# interface_board.net
KiCad netlist of a schematic drawn in EAGLE
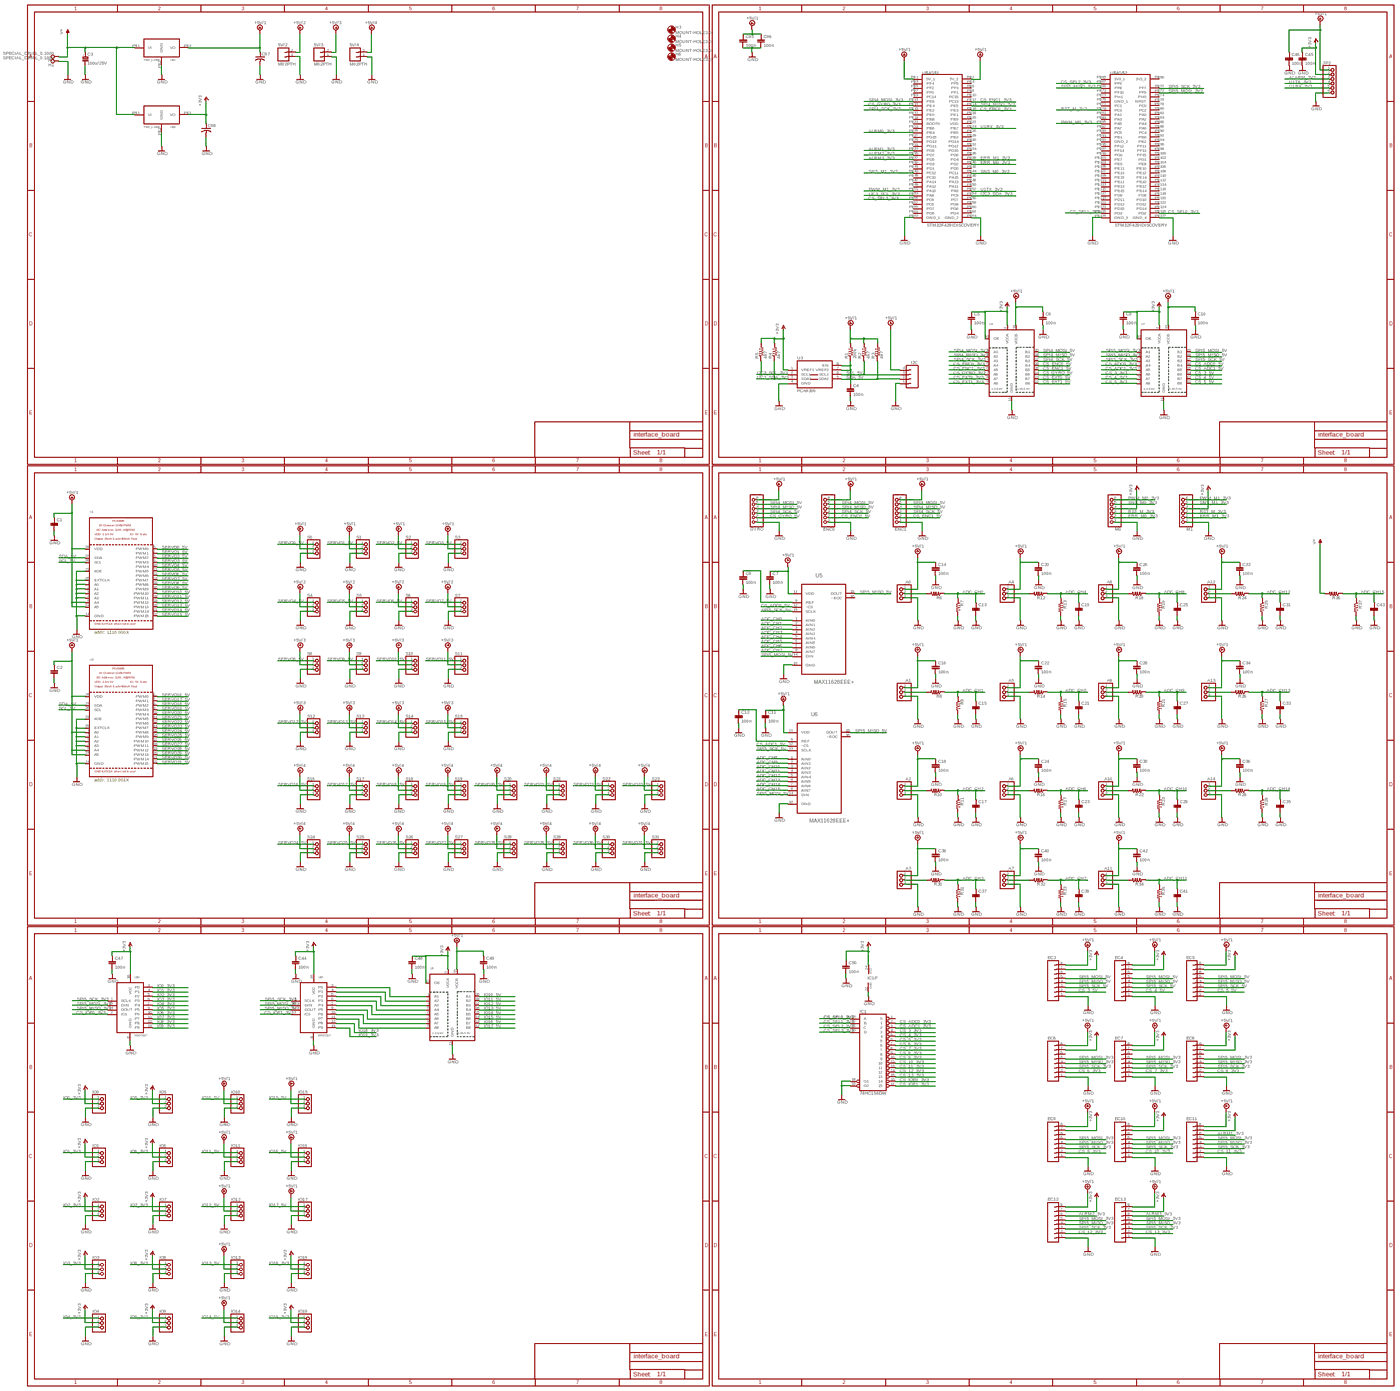
[diagram p0: schematic, sheet 1, overview]
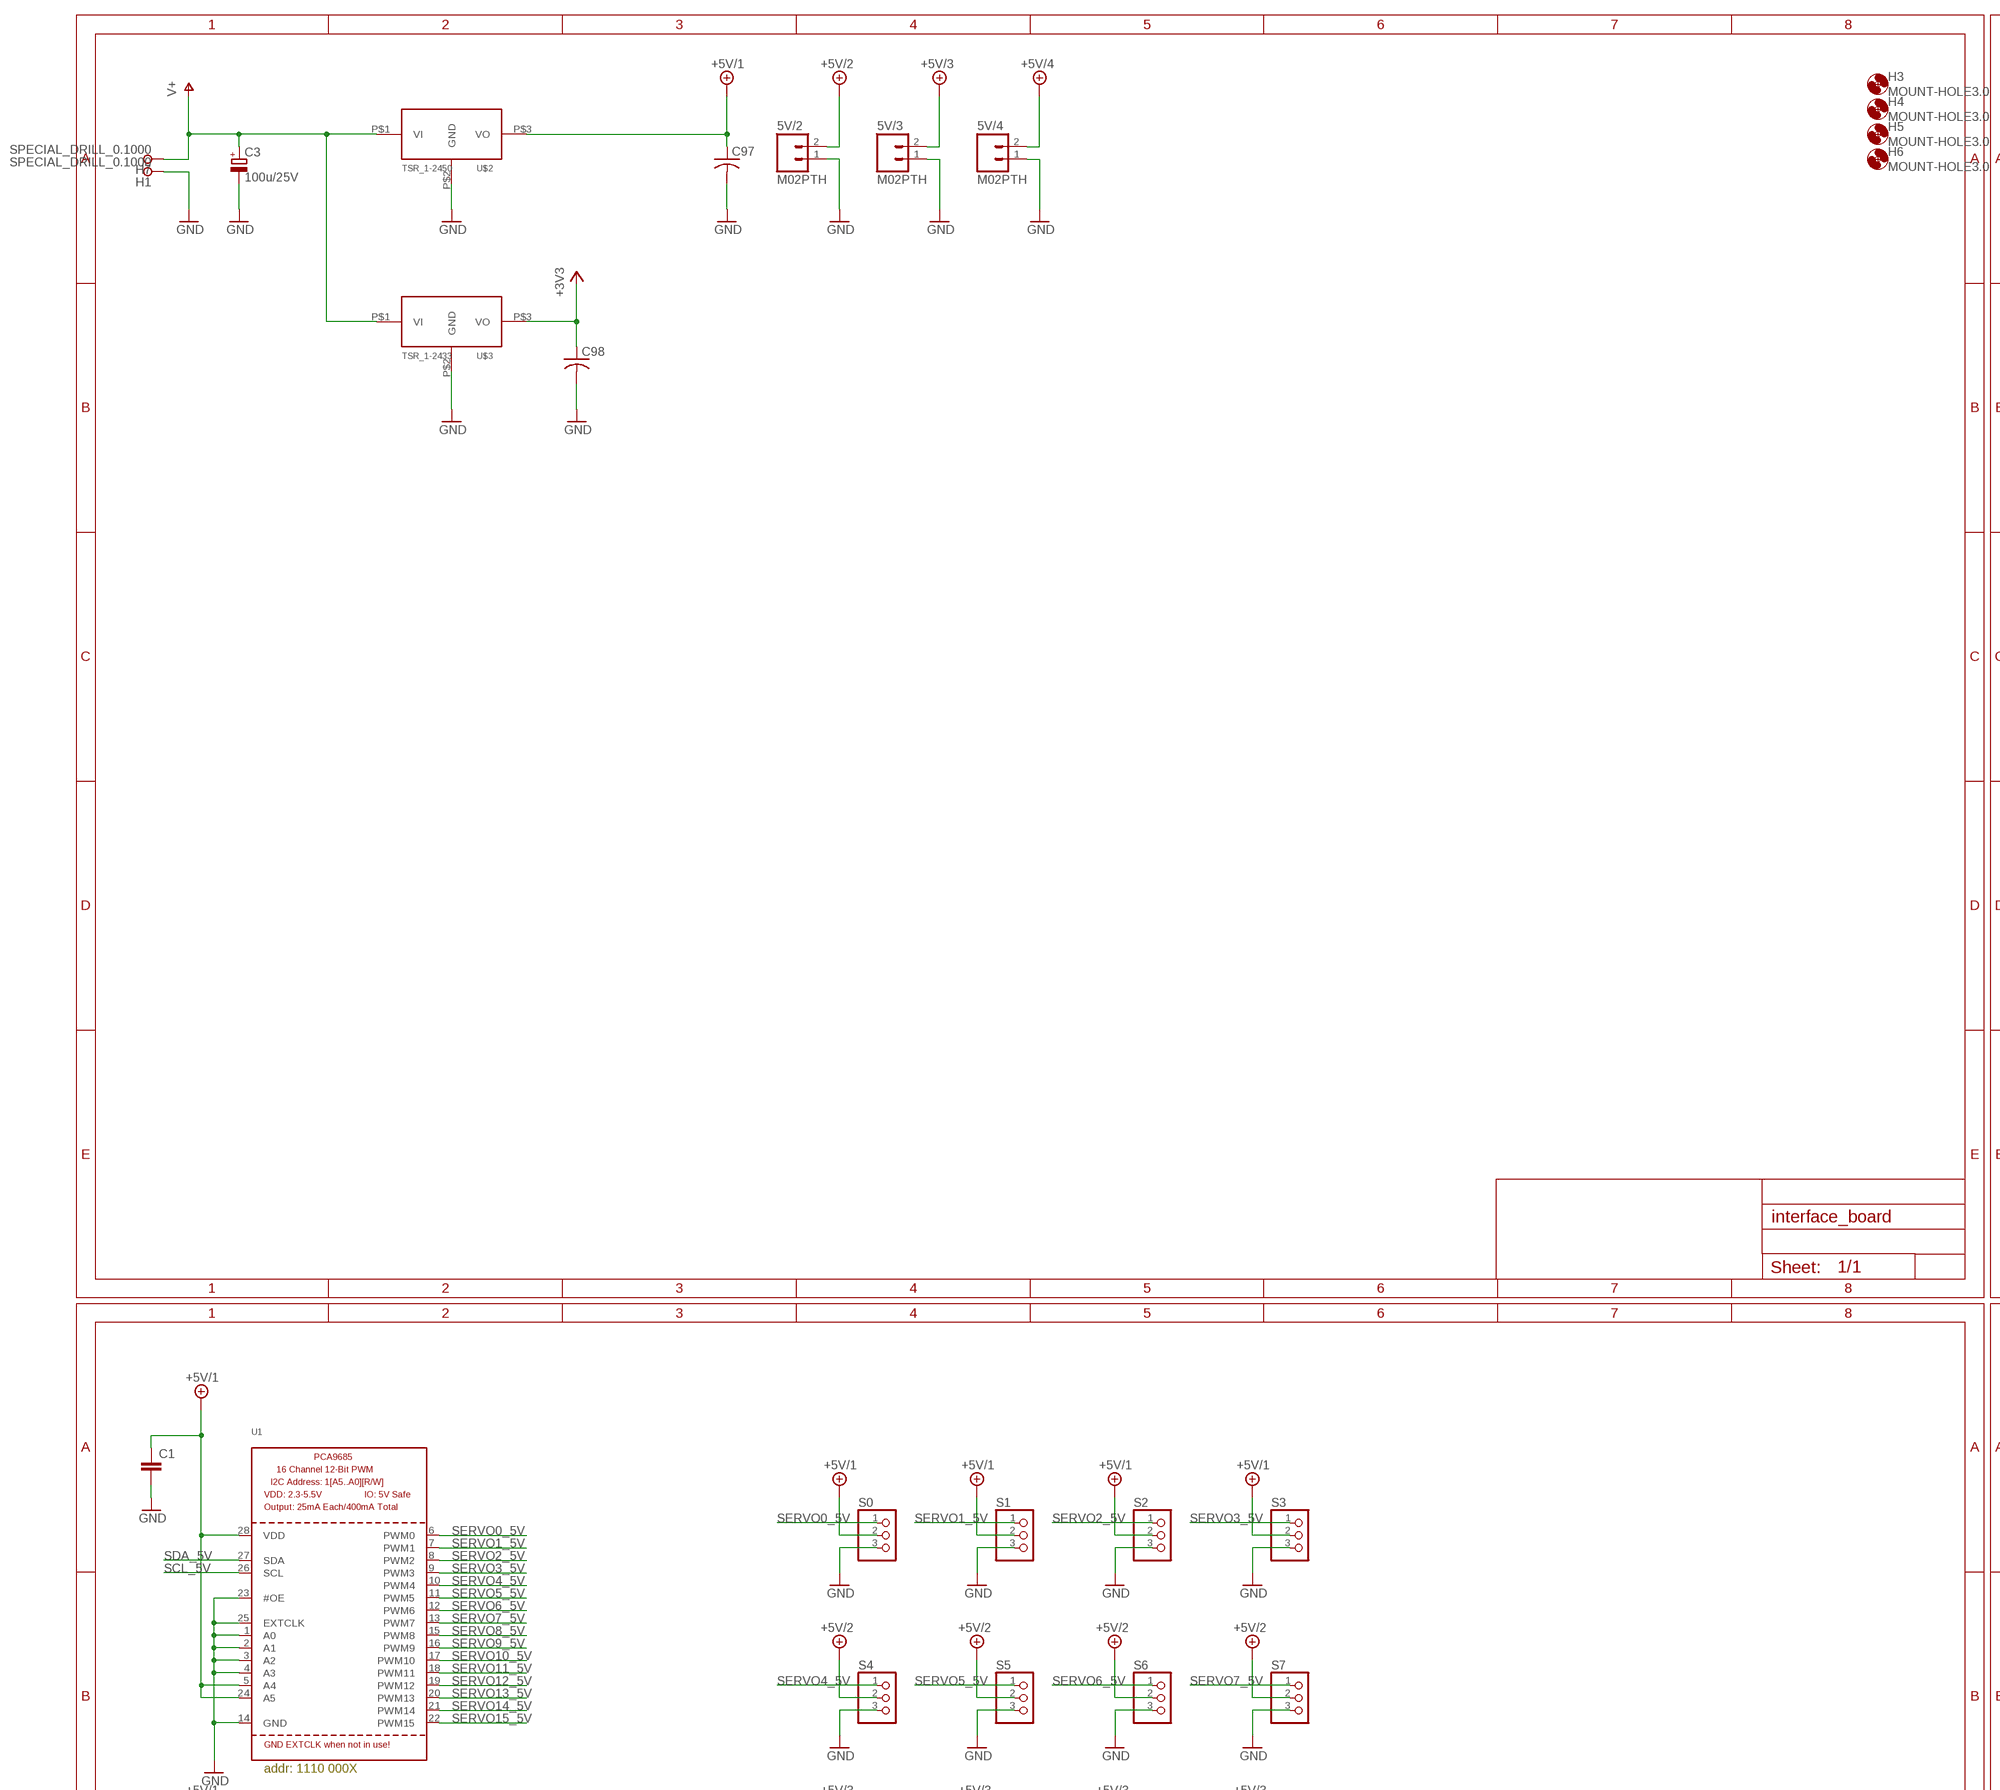
[diagram p1: schematic, sheet 1, part 1 of 4]
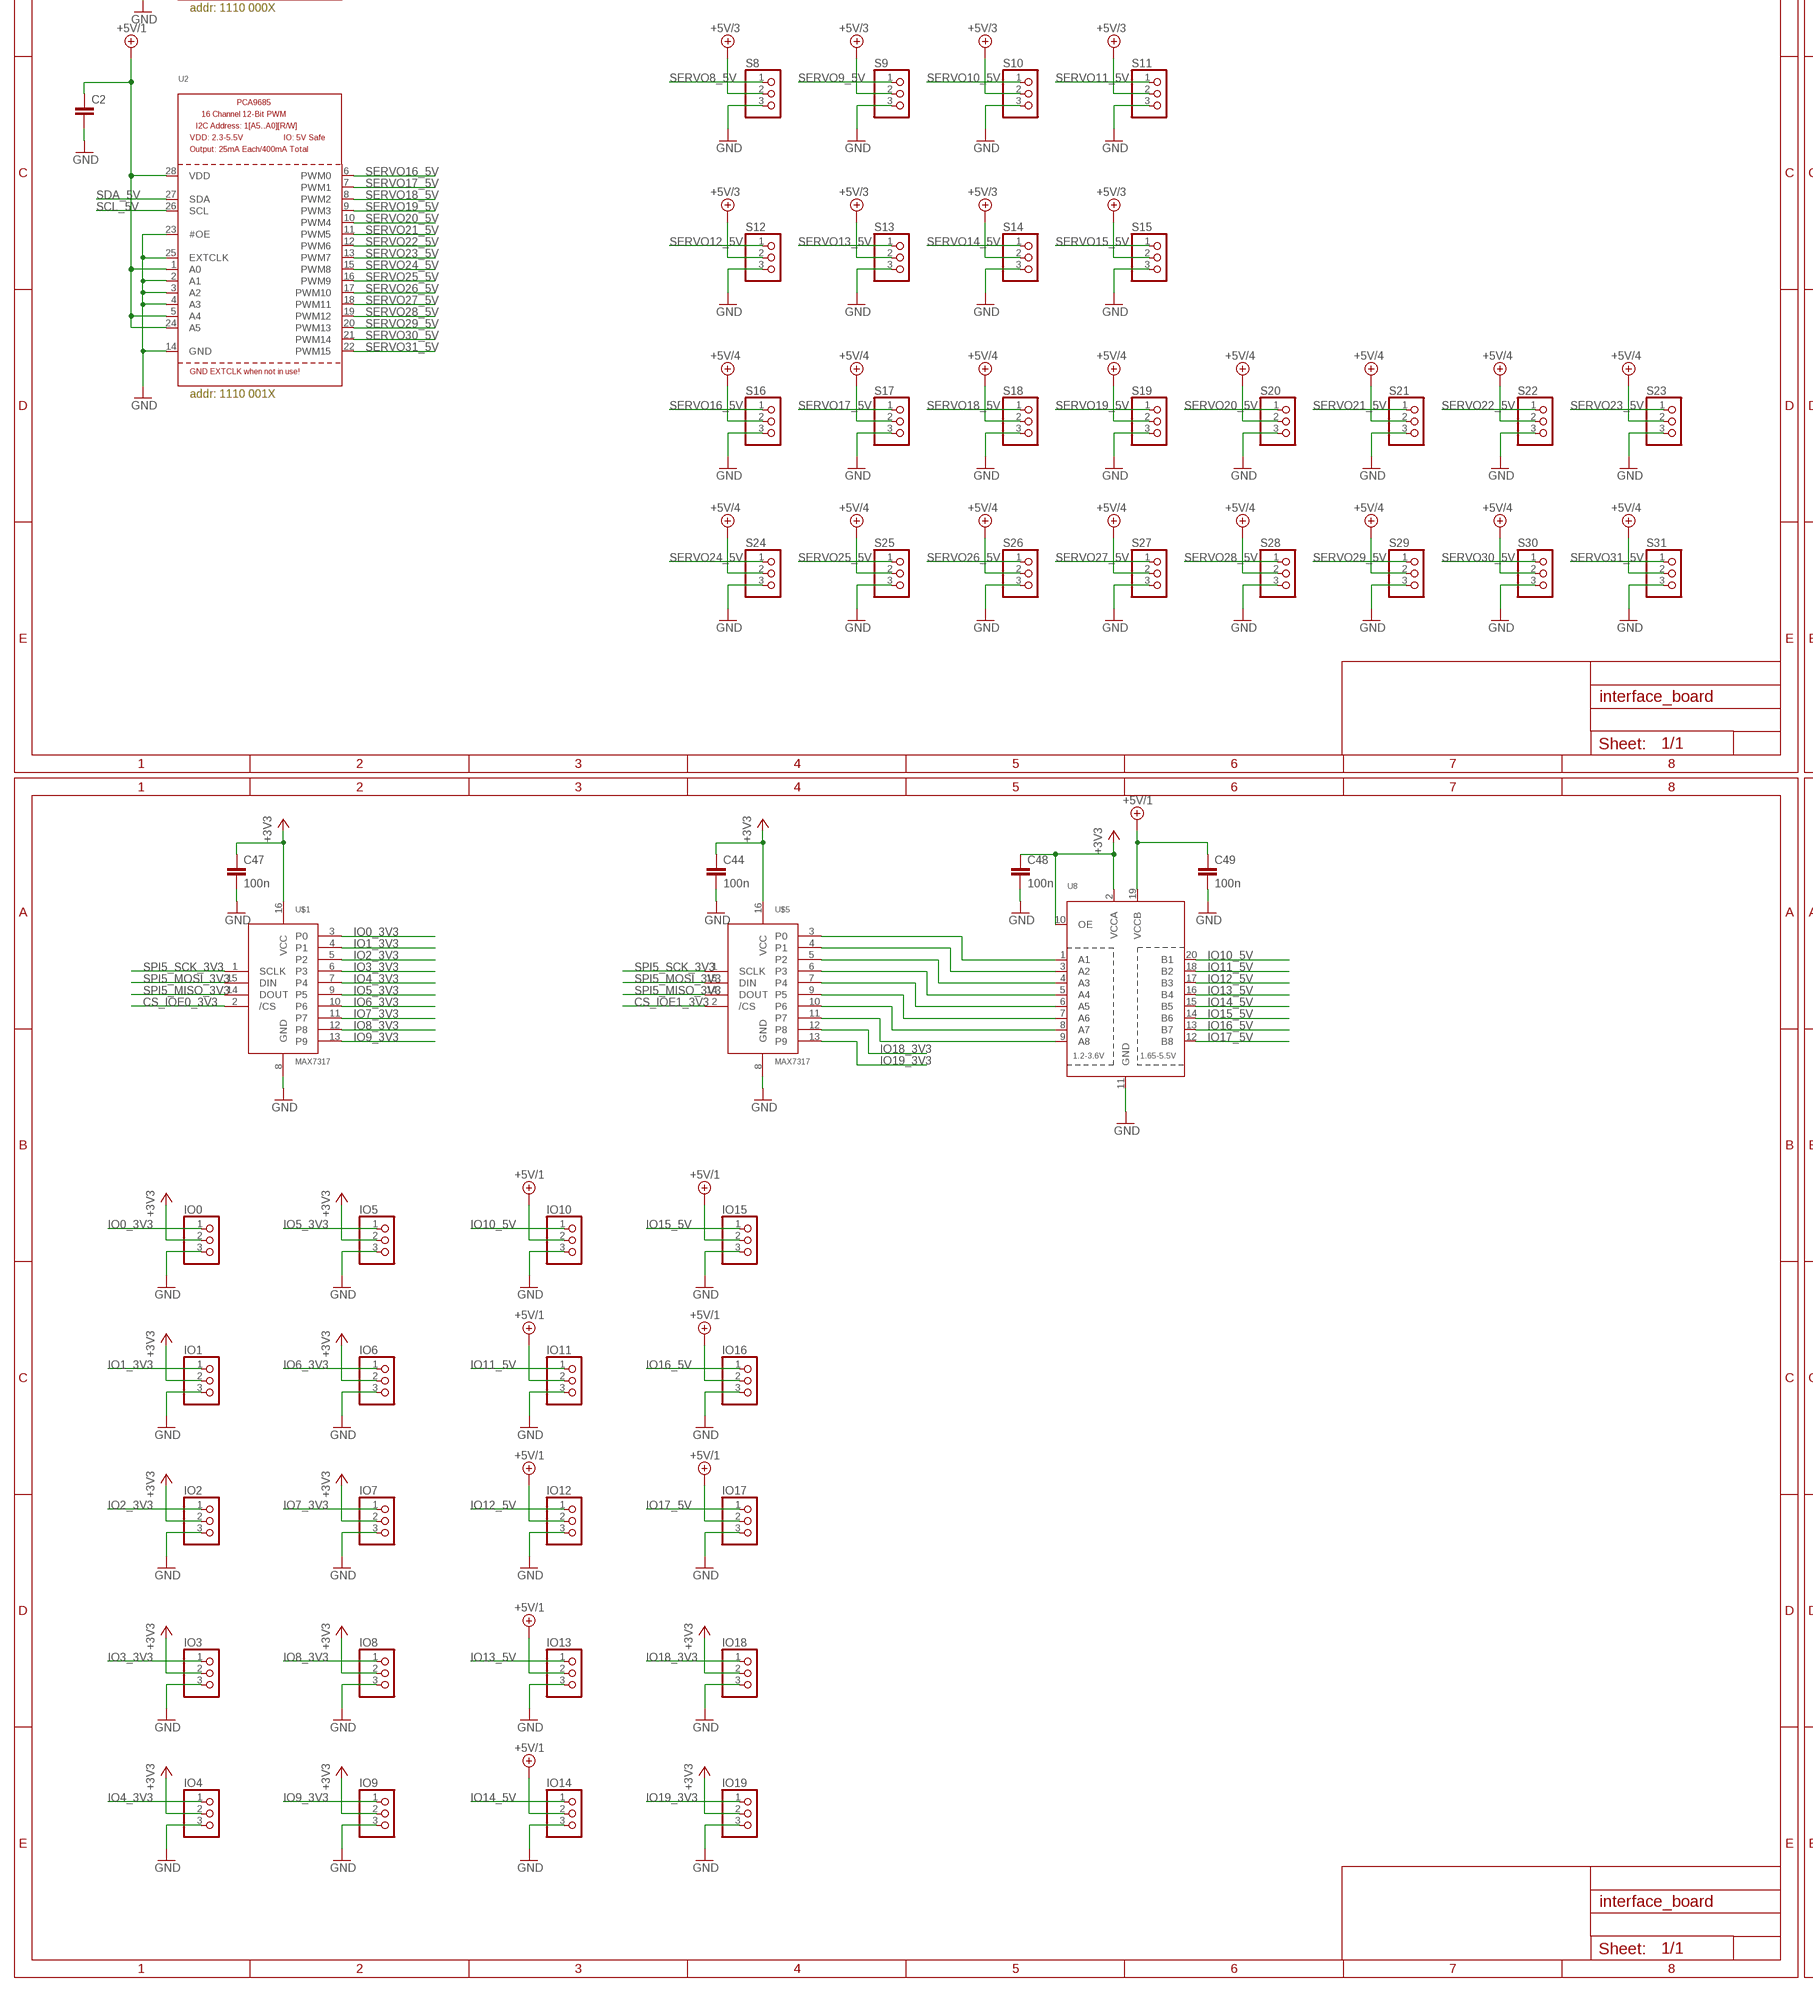
[diagram p2: schematic, sheet 1, part 2 of 4]
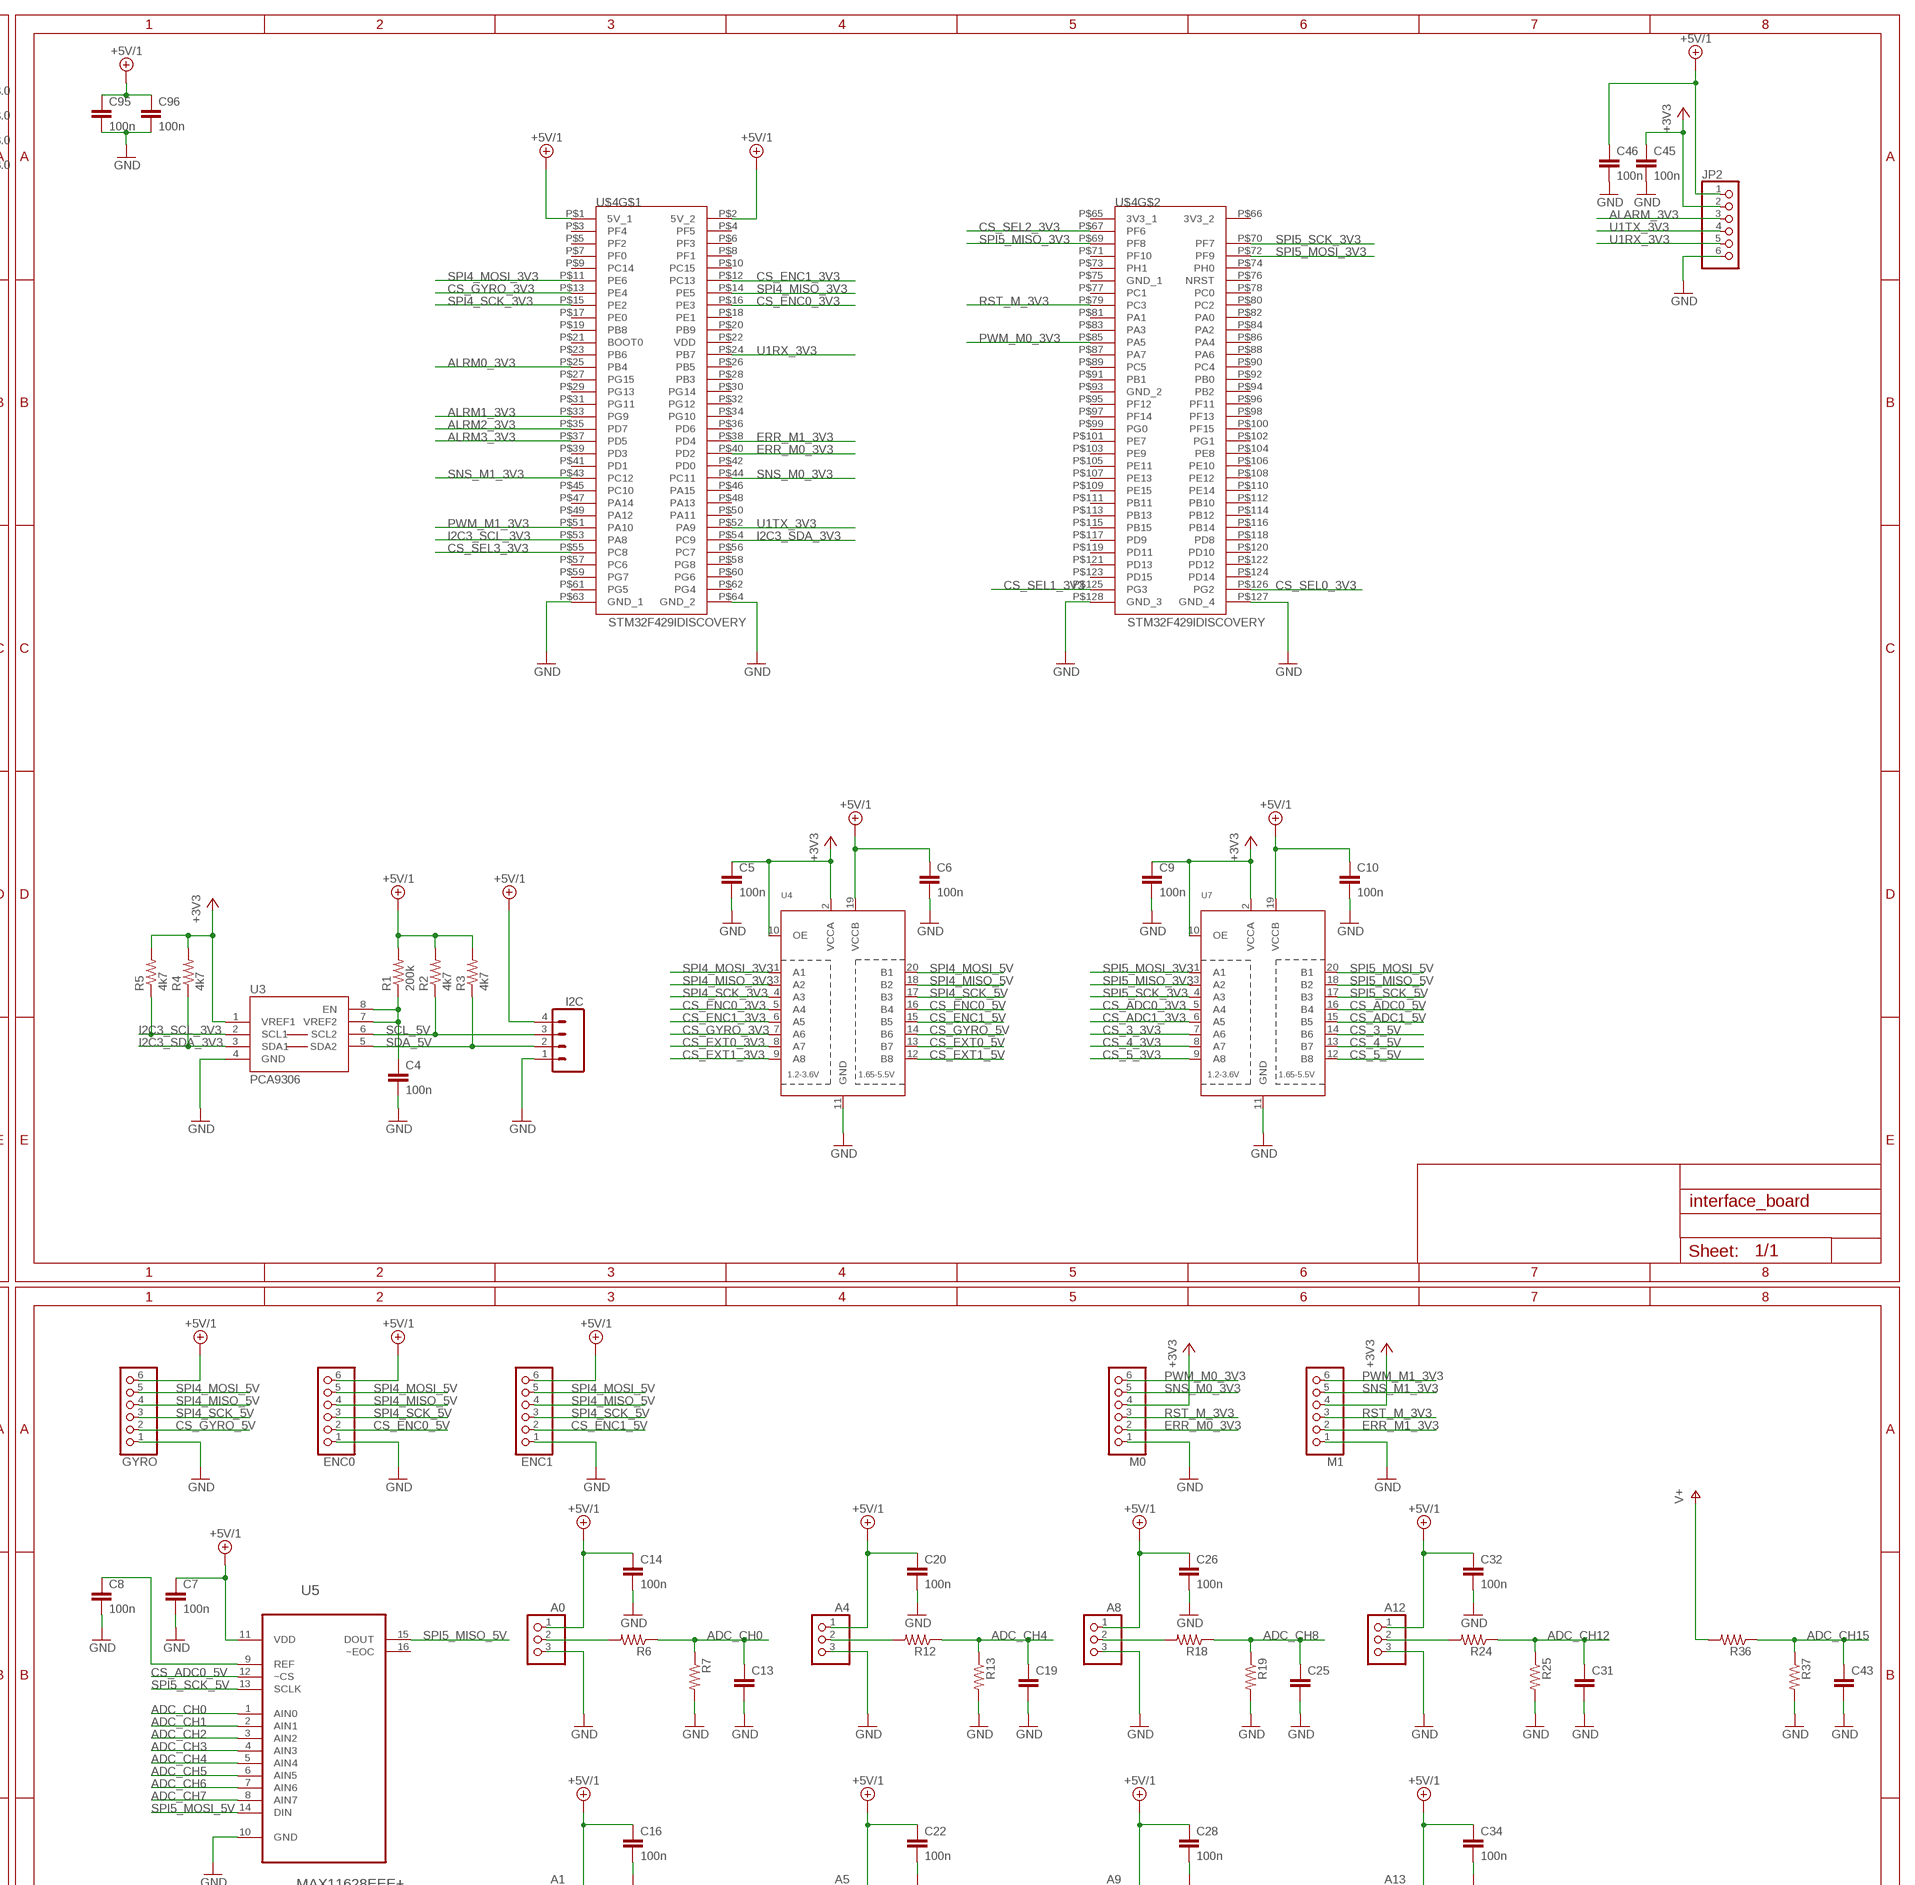
[diagram p3: schematic, sheet 1, part 3 of 4]
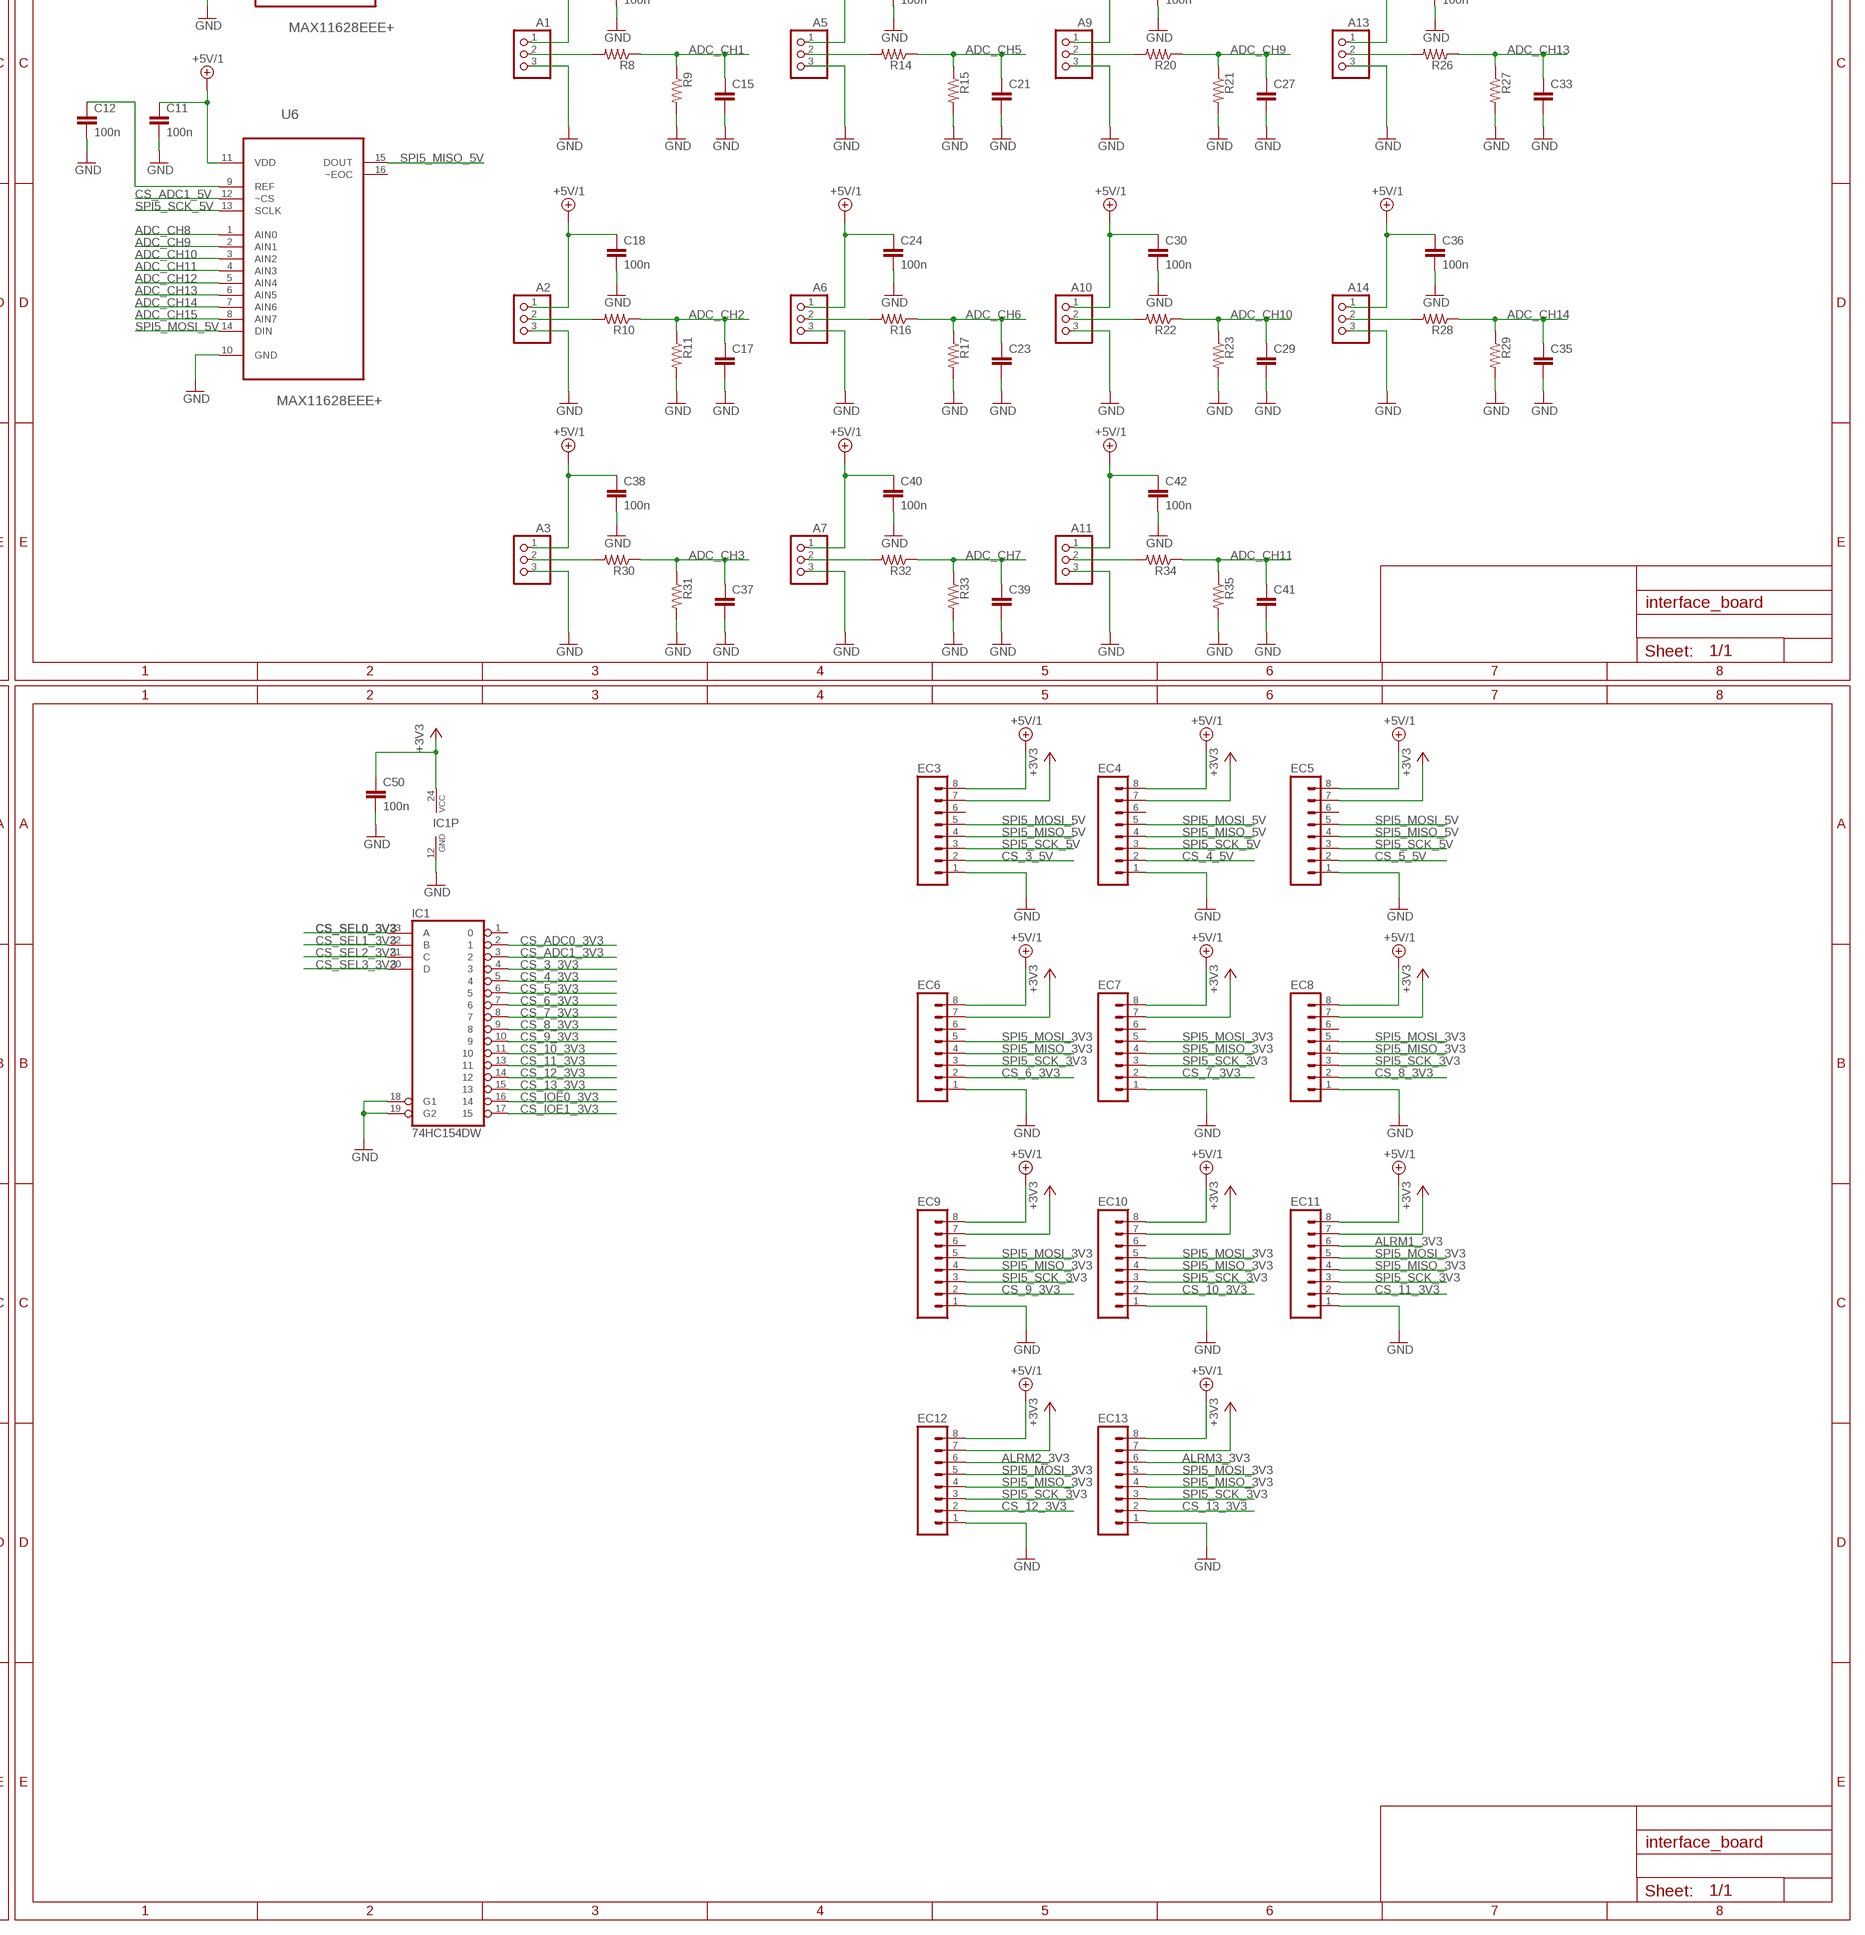
[diagram p4: schematic, sheet 1, part 4 of 4]

(export (version "E")
  (design (tool "Eeschema 10.0.6"))
  (components
    (comp (ref "5V/2")
      (value "M02PTH")
      (footprint "eagle-import:1X02")
      (libsource (lib "eagle-import") (part "M02PTH"))
    )
    (comp (ref "5V/3")
      (value "M02PTH")
      (footprint "eagle-import:1X02")
      (libsource (lib "eagle-import") (part "M02PTH"))
    )
    (comp (ref "5V/4")
      (value "M02PTH")
      (footprint "eagle-import:1X02")
      (libsource (lib "eagle-import") (part "M02PTH"))
    )
    (comp (ref "A0")
      (value "PINHD-1X3")
      (footprint "eagle-import:1X03")
      (libsource (lib "eagle-import") (part "PINHD-1X3"))
    )
    (comp (ref "A1")
      (value "PINHD-1X3")
      (footprint "eagle-import:1X03")
      (libsource (lib "eagle-import") (part "PINHD-1X3"))
    )
    (comp (ref "A2")
      (value "PINHD-1X3")
      (footprint "eagle-import:1X03")
      (libsource (lib "eagle-import") (part "PINHD-1X3"))
    )
    (comp (ref "A3")
      (value "PINHD-1X3")
      (footprint "eagle-import:1X03")
      (libsource (lib "eagle-import") (part "PINHD-1X3"))
    )
    (comp (ref "A4")
      (value "PINHD-1X3")
      (footprint "eagle-import:1X03")
      (libsource (lib "eagle-import") (part "PINHD-1X3"))
    )
    (comp (ref "A5")
      (value "PINHD-1X3")
      (footprint "eagle-import:1X03")
      (libsource (lib "eagle-import") (part "PINHD-1X3"))
    )
    (comp (ref "A6")
      (value "PINHD-1X3")
      (footprint "eagle-import:1X03")
      (libsource (lib "eagle-import") (part "PINHD-1X3"))
    )
    (comp (ref "A7")
      (value "PINHD-1X3")
      (footprint "eagle-import:1X03")
      (libsource (lib "eagle-import") (part "PINHD-1X3"))
    )
    (comp (ref "A8")
      (value "PINHD-1X3")
      (footprint "eagle-import:1X03")
      (libsource (lib "eagle-import") (part "PINHD-1X3"))
    )
    (comp (ref "A9")
      (value "PINHD-1X3")
      (footprint "eagle-import:1X03")
      (libsource (lib "eagle-import") (part "PINHD-1X3"))
    )
    (comp (ref "A10")
      (value "PINHD-1X3")
      (footprint "eagle-import:1X03")
      (libsource (lib "eagle-import") (part "PINHD-1X3"))
    )
    (comp (ref "A11")
      (value "PINHD-1X3")
      (footprint "eagle-import:1X03")
      (libsource (lib "eagle-import") (part "PINHD-1X3"))
    )
    (comp (ref "A12")
      (value "PINHD-1X3")
      (footprint "eagle-import:1X03")
      (libsource (lib "eagle-import") (part "PINHD-1X3"))
    )
    (comp (ref "A13")
      (value "PINHD-1X3")
      (footprint "eagle-import:1X03")
      (libsource (lib "eagle-import") (part "PINHD-1X3"))
    )
    (comp (ref "A14")
      (value "PINHD-1X3")
      (footprint "eagle-import:1X03")
      (libsource (lib "eagle-import") (part "PINHD-1X3"))
    )
    (comp (ref "C1")
      (value "C-EUC0603K")
      (footprint "eagle-import:C0603K")
      (libsource (lib "eagle-import") (part "C-EUC0603K"))
    )
    (comp (ref "C2")
      (value "C-EUC0603K")
      (footprint "eagle-import:C0603K")
      (libsource (lib "eagle-import") (part "C-EUC0603K"))
    )
    (comp (ref "C3")
      (value "100u/25V")
      (footprint "eagle-import:PANASONIC_E")
      (libsource (lib "eagle-import") (part "CPOL-EUE"))
    )
    (comp (ref "C4")
      (value "100n")
      (footprint "eagle-import:C0603K")
      (libsource (lib "eagle-import") (part "C-EUC0603K"))
    )
    (comp (ref "C5")
      (value "100n")
      (footprint "eagle-import:C0603K")
      (libsource (lib "eagle-import") (part "C-EUC0603K"))
    )
    (comp (ref "C6")
      (value "100n")
      (footprint "eagle-import:C0603K")
      (libsource (lib "eagle-import") (part "C-EUC0603K"))
    )
    (comp (ref "C7")
      (value "100n")
      (footprint "eagle-import:C0603K")
      (libsource (lib "eagle-import") (part "C-EUC0603K"))
    )
    (comp (ref "C8")
      (value "100n")
      (footprint "eagle-import:C0603K")
      (libsource (lib "eagle-import") (part "C-EUC0603K"))
    )
    (comp (ref "C9")
      (value "100n")
      (footprint "eagle-import:C0603K")
      (libsource (lib "eagle-import") (part "C-EUC0603K"))
    )
    (comp (ref "C10")
      (value "100n")
      (footprint "eagle-import:C0603K")
      (libsource (lib "eagle-import") (part "C-EUC0603K"))
    )
    (comp (ref "C11")
      (value "100n")
      (footprint "eagle-import:C0603K")
      (libsource (lib "eagle-import") (part "C-EUC0603K"))
    )
    (comp (ref "C12")
      (value "100n")
      (footprint "eagle-import:C0603K")
      (libsource (lib "eagle-import") (part "C-EUC0603K"))
    )
    (comp (ref "C13")
      (value "C-EUC0603K")
      (footprint "eagle-import:C0603K")
      (libsource (lib "eagle-import") (part "C-EUC0603K"))
    )
    (comp (ref "C14")
      (value "100n")
      (footprint "eagle-import:C0603K")
      (libsource (lib "eagle-import") (part "C-EUC0603K"))
    )
    (comp (ref "C15")
      (value "C-EUC0603K")
      (footprint "eagle-import:C0603K")
      (libsource (lib "eagle-import") (part "C-EUC0603K"))
    )
    (comp (ref "C16")
      (value "100n")
      (footprint "eagle-import:C0603K")
      (libsource (lib "eagle-import") (part "C-EUC0603K"))
    )
    (comp (ref "C17")
      (value "C-EUC0603K")
      (footprint "eagle-import:C0603K")
      (libsource (lib "eagle-import") (part "C-EUC0603K"))
    )
    (comp (ref "C18")
      (value "100n")
      (footprint "eagle-import:C0603K")
      (libsource (lib "eagle-import") (part "C-EUC0603K"))
    )
    (comp (ref "C19")
      (value "C-EUC0603K")
      (footprint "eagle-import:C0603K")
      (libsource (lib "eagle-import") (part "C-EUC0603K"))
    )
    (comp (ref "C20")
      (value "100n")
      (footprint "eagle-import:C0603K")
      (libsource (lib "eagle-import") (part "C-EUC0603K"))
    )
    (comp (ref "C21")
      (value "C-EUC0603K")
      (footprint "eagle-import:C0603K")
      (libsource (lib "eagle-import") (part "C-EUC0603K"))
    )
    (comp (ref "C22")
      (value "100n")
      (footprint "eagle-import:C0603K")
      (libsource (lib "eagle-import") (part "C-EUC0603K"))
    )
    (comp (ref "C23")
      (value "C-EUC0603K")
      (footprint "eagle-import:C0603K")
      (libsource (lib "eagle-import") (part "C-EUC0603K"))
    )
    (comp (ref "C24")
      (value "100n")
      (footprint "eagle-import:C0603K")
      (libsource (lib "eagle-import") (part "C-EUC0603K"))
    )
    (comp (ref "C25")
      (value "C-EUC0603K")
      (footprint "eagle-import:C0603K")
      (libsource (lib "eagle-import") (part "C-EUC0603K"))
    )
    (comp (ref "C26")
      (value "100n")
      (footprint "eagle-import:C0603K")
      (libsource (lib "eagle-import") (part "C-EUC0603K"))
    )
    (comp (ref "C27")
      (value "C-EUC0603K")
      (footprint "eagle-import:C0603K")
      (libsource (lib "eagle-import") (part "C-EUC0603K"))
    )
    (comp (ref "C28")
      (value "100n")
      (footprint "eagle-import:C0603K")
      (libsource (lib "eagle-import") (part "C-EUC0603K"))
    )
    (comp (ref "C29")
      (value "C-EUC0603K")
      (footprint "eagle-import:C0603K")
      (libsource (lib "eagle-import") (part "C-EUC0603K"))
    )
    (comp (ref "C30")
      (value "100n")
      (footprint "eagle-import:C0603K")
      (libsource (lib "eagle-import") (part "C-EUC0603K"))
    )
    (comp (ref "C31")
      (value "C-EUC0603K")
      (footprint "eagle-import:C0603K")
      (libsource (lib "eagle-import") (part "C-EUC0603K"))
    )
    (comp (ref "C32")
      (value "100n")
      (footprint "eagle-import:C0603K")
      (libsource (lib "eagle-import") (part "C-EUC0603K"))
    )
    (comp (ref "C33")
      (value "C-EUC0603K")
      (footprint "eagle-import:C0603K")
      (libsource (lib "eagle-import") (part "C-EUC0603K"))
    )
    (comp (ref "C34")
      (value "100n")
      (footprint "eagle-import:C0603K")
      (libsource (lib "eagle-import") (part "C-EUC0603K"))
    )
    (comp (ref "C35")
      (value "C-EUC0603K")
      (footprint "eagle-import:C0603K")
      (libsource (lib "eagle-import") (part "C-EUC0603K"))
    )
    (comp (ref "C36")
      (value "100n")
      (footprint "eagle-import:C0603K")
      (libsource (lib "eagle-import") (part "C-EUC0603K"))
    )
    (comp (ref "C37")
      (value "C-EUC0603K")
      (footprint "eagle-import:C0603K")
      (libsource (lib "eagle-import") (part "C-EUC0603K"))
    )
    (comp (ref "C38")
      (value "100n")
      (footprint "eagle-import:C0603K")
      (libsource (lib "eagle-import") (part "C-EUC0603K"))
    )
    (comp (ref "C39")
      (value "C-EUC0603K")
      (footprint "eagle-import:C0603K")
      (libsource (lib "eagle-import") (part "C-EUC0603K"))
    )
    (comp (ref "C40")
      (value "100n")
      (footprint "eagle-import:C0603K")
      (libsource (lib "eagle-import") (part "C-EUC0603K"))
    )
    (comp (ref "C41")
      (value "C-EUC0603K")
      (footprint "eagle-import:C0603K")
      (libsource (lib "eagle-import") (part "C-EUC0603K"))
    )
    (comp (ref "C42")
      (value "100n")
      (footprint "eagle-import:C0603K")
      (libsource (lib "eagle-import") (part "C-EUC0603K"))
    )
    (comp (ref "C43")
      (value "C-EUC0603K")
      (footprint "eagle-import:C0603K")
      (libsource (lib "eagle-import") (part "C-EUC0603K"))
    )
    (comp (ref "C44")
      (value "100n")
      (footprint "eagle-import:C0603K")
      (libsource (lib "eagle-import") (part "C-EUC0603K"))
    )
    (comp (ref "C45")
      (value "100n")
      (footprint "eagle-import:C0603K")
      (libsource (lib "eagle-import") (part "C-EUC0603K"))
    )
    (comp (ref "C46")
      (value "100n")
      (footprint "eagle-import:C0603K")
      (libsource (lib "eagle-import") (part "C-EUC0603K"))
    )
    (comp (ref "C47")
      (value "100n")
      (footprint "eagle-import:C0603K")
      (libsource (lib "eagle-import") (part "C-EUC0603K"))
    )
    (comp (ref "C48")
      (value "100n")
      (footprint "eagle-import:C0603K")
      (libsource (lib "eagle-import") (part "C-EUC0603K"))
    )
    (comp (ref "C49")
      (value "100n")
      (footprint "eagle-import:C0603K")
      (libsource (lib "eagle-import") (part "C-EUC0603K"))
    )
    (comp (ref "C50")
      (value "100n")
      (footprint "eagle-import:C0603K")
      (libsource (lib "eagle-import") (part "C-EUC0603K"))
    )
    (comp (ref "C95")
      (value "100n")
      (footprint "eagle-import:C0603K")
      (libsource (lib "eagle-import") (part "C-EUC0603K"))
    )
    (comp (ref "C96")
      (value "100n")
      (footprint "eagle-import:C0603K")
      (libsource (lib "eagle-import") (part "C-EUC0603K"))
    )
    (comp (ref "C97")
      (value "C-USC0805")
      (footprint "eagle-import:C0805")
      (libsource (lib "eagle-import") (part "C-USC0805"))
    )
    (comp (ref "C98")
      (value "C-USC0805")
      (footprint "eagle-import:C0805")
      (libsource (lib "eagle-import") (part "C-USC0805"))
    )
    (comp (ref "EC3")
      (value "M081X08")
      (footprint "eagle-import:1X08")
      (libsource (lib "eagle-import") (part "M081X08"))
    )
    (comp (ref "EC4")
      (value "M081X08")
      (footprint "eagle-import:1X08")
      (libsource (lib "eagle-import") (part "M081X08"))
    )
    (comp (ref "EC5")
      (value "M081X08")
      (footprint "eagle-import:1X08")
      (libsource (lib "eagle-import") (part "M081X08"))
    )
    (comp (ref "EC6")
      (value "M081X08")
      (footprint "eagle-import:1X08")
      (libsource (lib "eagle-import") (part "M081X08"))
    )
    (comp (ref "EC7")
      (value "M081X08")
      (footprint "eagle-import:1X08")
      (libsource (lib "eagle-import") (part "M081X08"))
    )
    (comp (ref "EC8")
      (value "M081X08")
      (footprint "eagle-import:1X08")
      (libsource (lib "eagle-import") (part "M081X08"))
    )
    (comp (ref "EC9")
      (value "M081X08")
      (footprint "eagle-import:1X08")
      (libsource (lib "eagle-import") (part "M081X08"))
    )
    (comp (ref "EC10")
      (value "M081X08")
      (footprint "eagle-import:1X08")
      (libsource (lib "eagle-import") (part "M081X08"))
    )
    (comp (ref "EC11")
      (value "M081X08")
      (footprint "eagle-import:1X08")
      (libsource (lib "eagle-import") (part "M081X08"))
    )
    (comp (ref "EC12")
      (value "M081X08")
      (footprint "eagle-import:1X08")
      (libsource (lib "eagle-import") (part "M081X08"))
    )
    (comp (ref "EC13")
      (value "M081X08")
      (footprint "eagle-import:1X08")
      (libsource (lib "eagle-import") (part "M081X08"))
    )
    (comp (ref "ENC0")
      (value "PINHD-1X6")
      (footprint "eagle-import:1X06")
      (libsource (lib "eagle-import") (part "PINHD-1X6"))
    )
    (comp (ref "ENC1")
      (value "PINHD-1X6")
      (footprint "eagle-import:1X06")
      (libsource (lib "eagle-import") (part "PINHD-1X6"))
    )
    (comp (ref "GYRO")
      (value "PINHD-1X6")
      (footprint "eagle-import:1X06")
      (libsource (lib "eagle-import") (part "PINHD-1X6"))
    )
    (comp (ref "H1")
      (value "SPECIAL_DRILL_0.1000")
      (footprint "eagle-import:PAD_0.1000")
      (libsource (lib "eagle-import") (part "SPECIAL_DRILL_0.1000"))
    )
    (comp (ref "H3")
      (value "MOUNT-HOLE3.0")
      (footprint "eagle-import:3,0")
      (libsource (lib "eagle-import") (part "MOUNT-HOLE3.0"))
    )
    (comp (ref "H4")
      (value "MOUNT-HOLE3.0")
      (footprint "eagle-import:3,0")
      (libsource (lib "eagle-import") (part "MOUNT-HOLE3.0"))
    )
    (comp (ref "H5")
      (value "MOUNT-HOLE3.0")
      (footprint "eagle-import:3,0")
      (libsource (lib "eagle-import") (part "MOUNT-HOLE3.0"))
    )
    (comp (ref "H6")
      (value "MOUNT-HOLE3.0")
      (footprint "eagle-import:3,0")
      (libsource (lib "eagle-import") (part "MOUNT-HOLE3.0"))
    )
    (comp (ref "H7")
      (value "SPECIAL_DRILL_0.1000")
      (footprint "eagle-import:PAD_0.1000")
      (libsource (lib "eagle-import") (part "SPECIAL_DRILL_0.1000"))
    )
    (comp (ref "I2C")
      (value "M04PTH")
      (footprint "eagle-import:1X04")
      (libsource (lib "eagle-import") (part "M04PTH"))
    )
    (comp (ref "IC1")
      (value "74HC154DW")
      (footprint "eagle-import:SO24W")
      (libsource (lib "eagle-import") (part "74154DWHC"))
    )
    (comp (ref "IO0")
      (value "PINHD-1X3")
      (footprint "eagle-import:1X03")
      (libsource (lib "eagle-import") (part "PINHD-1X3"))
    )
    (comp (ref "IO1")
      (value "PINHD-1X3")
      (footprint "eagle-import:1X03")
      (libsource (lib "eagle-import") (part "PINHD-1X3"))
    )
    (comp (ref "IO2")
      (value "PINHD-1X3")
      (footprint "eagle-import:1X03")
      (libsource (lib "eagle-import") (part "PINHD-1X3"))
    )
    (comp (ref "IO3")
      (value "PINHD-1X3")
      (footprint "eagle-import:1X03")
      (libsource (lib "eagle-import") (part "PINHD-1X3"))
    )
    (comp (ref "IO4")
      (value "PINHD-1X3")
      (footprint "eagle-import:1X03")
      (libsource (lib "eagle-import") (part "PINHD-1X3"))
    )
    (comp (ref "IO5")
      (value "PINHD-1X3")
      (footprint "eagle-import:1X03")
      (libsource (lib "eagle-import") (part "PINHD-1X3"))
    )
    (comp (ref "IO6")
      (value "PINHD-1X3")
      (footprint "eagle-import:1X03")
      (libsource (lib "eagle-import") (part "PINHD-1X3"))
    )
    (comp (ref "IO7")
      (value "PINHD-1X3")
      (footprint "eagle-import:1X03")
      (libsource (lib "eagle-import") (part "PINHD-1X3"))
    )
    (comp (ref "IO8")
      (value "PINHD-1X3")
      (footprint "eagle-import:1X03")
      (libsource (lib "eagle-import") (part "PINHD-1X3"))
    )
    (comp (ref "IO9")
      (value "PINHD-1X3")
      (footprint "eagle-import:1X03")
      (libsource (lib "eagle-import") (part "PINHD-1X3"))
    )
    (comp (ref "IO10")
      (value "PINHD-1X3")
      (footprint "eagle-import:1X03")
      (libsource (lib "eagle-import") (part "PINHD-1X3"))
    )
    (comp (ref "IO11")
      (value "PINHD-1X3")
      (footprint "eagle-import:1X03")
      (libsource (lib "eagle-import") (part "PINHD-1X3"))
    )
    (comp (ref "IO12")
      (value "PINHD-1X3")
      (footprint "eagle-import:1X03")
      (libsource (lib "eagle-import") (part "PINHD-1X3"))
    )
    (comp (ref "IO13")
      (value "PINHD-1X3")
      (footprint "eagle-import:1X03")
      (libsource (lib "eagle-import") (part "PINHD-1X3"))
    )
    (comp (ref "IO14")
      (value "PINHD-1X3")
      (footprint "eagle-import:1X03")
      (libsource (lib "eagle-import") (part "PINHD-1X3"))
    )
    (comp (ref "IO15")
      (value "PINHD-1X3")
      (footprint "eagle-import:1X03")
      (libsource (lib "eagle-import") (part "PINHD-1X3"))
    )
    (comp (ref "IO16")
      (value "PINHD-1X3")
      (footprint "eagle-import:1X03")
      (libsource (lib "eagle-import") (part "PINHD-1X3"))
    )
    (comp (ref "IO17")
      (value "PINHD-1X3")
      (footprint "eagle-import:1X03")
      (libsource (lib "eagle-import") (part "PINHD-1X3"))
    )
    (comp (ref "IO18")
      (value "PINHD-1X3")
      (footprint "eagle-import:1X03")
      (libsource (lib "eagle-import") (part "PINHD-1X3"))
    )
    (comp (ref "IO19")
      (value "PINHD-1X3")
      (footprint "eagle-import:1X03")
      (libsource (lib "eagle-import") (part "PINHD-1X3"))
    )
    (comp (ref "JP2")
      (value "PINHD-1X6B")
      (footprint "eagle-import:1X06-BIG")
      (libsource (lib "eagle-import") (part "PINHD-1X6B"))
    )
    (comp (ref "M0")
      (value "PINHD-1X6")
      (footprint "eagle-import:1X06")
      (libsource (lib "eagle-import") (part "PINHD-1X6"))
    )
    (comp (ref "M1")
      (value "PINHD-1X6")
      (footprint "eagle-import:1X06")
      (libsource (lib "eagle-import") (part "PINHD-1X6"))
    )
    (comp (ref "R1")
      (value "200k")
      (footprint "eagle-import:R0603")
      (libsource (lib "eagle-import") (part "R-US_R0603"))
    )
    (comp (ref "R2")
      (value "4k7")
      (footprint "eagle-import:R0603")
      (libsource (lib "eagle-import") (part "R-US_R0603"))
    )
    (comp (ref "R3")
      (value "4k7")
      (footprint "eagle-import:R0603")
      (libsource (lib "eagle-import") (part "R-US_R0603"))
    )
    (comp (ref "R4")
      (value "4k7")
      (footprint "eagle-import:R0603")
      (libsource (lib "eagle-import") (part "R-US_R0603"))
    )
    (comp (ref "R5")
      (value "4k7")
      (footprint "eagle-import:R0603")
      (libsource (lib "eagle-import") (part "R-US_R0603"))
    )
    (comp (ref "R6")
      (value "R-US_R0603")
      (footprint "eagle-import:R0603")
      (libsource (lib "eagle-import") (part "R-US_R0603"))
    )
    (comp (ref "R7")
      (value "R-US_R0603")
      (footprint "eagle-import:R0603")
      (libsource (lib "eagle-import") (part "R-US_R0603"))
    )
    (comp (ref "R8")
      (value "R-US_R0603")
      (footprint "eagle-import:R0603")
      (libsource (lib "eagle-import") (part "R-US_R0603"))
    )
    (comp (ref "R9")
      (value "R-US_R0603")
      (footprint "eagle-import:R0603")
      (libsource (lib "eagle-import") (part "R-US_R0603"))
    )
    (comp (ref "R10")
      (value "R-US_R0603")
      (footprint "eagle-import:R0603")
      (libsource (lib "eagle-import") (part "R-US_R0603"))
    )
    (comp (ref "R11")
      (value "R-US_R0603")
      (footprint "eagle-import:R0603")
      (libsource (lib "eagle-import") (part "R-US_R0603"))
    )
    (comp (ref "R12")
      (value "R-US_R0603")
      (footprint "eagle-import:R0603")
      (libsource (lib "eagle-import") (part "R-US_R0603"))
    )
    (comp (ref "R13")
      (value "R-US_R0603")
      (footprint "eagle-import:R0603")
      (libsource (lib "eagle-import") (part "R-US_R0603"))
    )
    (comp (ref "R14")
      (value "R-US_R0603")
      (footprint "eagle-import:R0603")
      (libsource (lib "eagle-import") (part "R-US_R0603"))
    )
    (comp (ref "R15")
      (value "R-US_R0603")
      (footprint "eagle-import:R0603")
      (libsource (lib "eagle-import") (part "R-US_R0603"))
    )
    (comp (ref "R16")
      (value "R-US_R0603")
      (footprint "eagle-import:R0603")
      (libsource (lib "eagle-import") (part "R-US_R0603"))
    )
    (comp (ref "R17")
      (value "R-US_R0603")
      (footprint "eagle-import:R0603")
      (libsource (lib "eagle-import") (part "R-US_R0603"))
    )
    (comp (ref "R18")
      (value "R-US_R0603")
      (footprint "eagle-import:R0603")
      (libsource (lib "eagle-import") (part "R-US_R0603"))
    )
    (comp (ref "R19")
      (value "R-US_R0603")
      (footprint "eagle-import:R0603")
      (libsource (lib "eagle-import") (part "R-US_R0603"))
    )
    (comp (ref "R20")
      (value "R-US_R0603")
      (footprint "eagle-import:R0603")
      (libsource (lib "eagle-import") (part "R-US_R0603"))
    )
    (comp (ref "R21")
      (value "R-US_R0603")
      (footprint "eagle-import:R0603")
      (libsource (lib "eagle-import") (part "R-US_R0603"))
    )
    (comp (ref "R22")
      (value "R-US_R0603")
      (footprint "eagle-import:R0603")
      (libsource (lib "eagle-import") (part "R-US_R0603"))
    )
    (comp (ref "R23")
      (value "R-US_R0603")
      (footprint "eagle-import:R0603")
      (libsource (lib "eagle-import") (part "R-US_R0603"))
    )
    (comp (ref "R24")
      (value "R-US_R0603")
      (footprint "eagle-import:R0603")
      (libsource (lib "eagle-import") (part "R-US_R0603"))
    )
    (comp (ref "R25")
      (value "R-US_R0603")
      (footprint "eagle-import:R0603")
      (libsource (lib "eagle-import") (part "R-US_R0603"))
    )
    (comp (ref "R26")
      (value "R-US_R0603")
      (footprint "eagle-import:R0603")
      (libsource (lib "eagle-import") (part "R-US_R0603"))
    )
    (comp (ref "R27")
      (value "R-US_R0603")
      (footprint "eagle-import:R0603")
      (libsource (lib "eagle-import") (part "R-US_R0603"))
    )
    (comp (ref "R28")
      (value "R-US_R0603")
      (footprint "eagle-import:R0603")
      (libsource (lib "eagle-import") (part "R-US_R0603"))
    )
    (comp (ref "R29")
      (value "R-US_R0603")
      (footprint "eagle-import:R0603")
      (libsource (lib "eagle-import") (part "R-US_R0603"))
    )
    (comp (ref "R30")
      (value "R-US_R0603")
      (footprint "eagle-import:R0603")
      (libsource (lib "eagle-import") (part "R-US_R0603"))
    )
    (comp (ref "R31")
      (value "R-US_R0603")
      (footprint "eagle-import:R0603")
      (libsource (lib "eagle-import") (part "R-US_R0603"))
    )
    (comp (ref "R32")
      (value "R-US_R0603")
      (footprint "eagle-import:R0603")
      (libsource (lib "eagle-import") (part "R-US_R0603"))
    )
    (comp (ref "R33")
      (value "R-US_R0603")
      (footprint "eagle-import:R0603")
      (libsource (lib "eagle-import") (part "R-US_R0603"))
    )
    (comp (ref "R34")
      (value "R-US_R0603")
      (footprint "eagle-import:R0603")
      (libsource (lib "eagle-import") (part "R-US_R0603"))
    )
    (comp (ref "R35")
      (value "R-US_R0603")
      (footprint "eagle-import:R0603")
      (libsource (lib "eagle-import") (part "R-US_R0603"))
    )
    (comp (ref "R36")
      (value "R-US_R0603")
      (footprint "eagle-import:R0603")
      (libsource (lib "eagle-import") (part "R-US_R0603"))
    )
    (comp (ref "R37")
      (value "R-US_R0603")
      (footprint "eagle-import:R0603")
      (libsource (lib "eagle-import") (part "R-US_R0603"))
    )
    (comp (ref "S0")
      (value "PINHD-1X3")
      (footprint "eagle-import:1X03")
      (libsource (lib "eagle-import") (part "PINHD-1X3"))
    )
    (comp (ref "S1")
      (value "PINHD-1X3")
      (footprint "eagle-import:1X03")
      (libsource (lib "eagle-import") (part "PINHD-1X3"))
    )
    (comp (ref "S2")
      (value "PINHD-1X3")
      (footprint "eagle-import:1X03")
      (libsource (lib "eagle-import") (part "PINHD-1X3"))
    )
    (comp (ref "S3")
      (value "PINHD-1X3")
      (footprint "eagle-import:1X03")
      (libsource (lib "eagle-import") (part "PINHD-1X3"))
    )
    (comp (ref "S4")
      (value "PINHD-1X3")
      (footprint "eagle-import:1X03")
      (libsource (lib "eagle-import") (part "PINHD-1X3"))
    )
    (comp (ref "S5")
      (value "PINHD-1X3")
      (footprint "eagle-import:1X03")
      (libsource (lib "eagle-import") (part "PINHD-1X3"))
    )
    (comp (ref "S6")
      (value "PINHD-1X3")
      (footprint "eagle-import:1X03")
      (libsource (lib "eagle-import") (part "PINHD-1X3"))
    )
    (comp (ref "S7")
      (value "PINHD-1X3")
      (footprint "eagle-import:1X03")
      (libsource (lib "eagle-import") (part "PINHD-1X3"))
    )
    (comp (ref "S8")
      (value "PINHD-1X3")
      (footprint "eagle-import:1X03")
      (libsource (lib "eagle-import") (part "PINHD-1X3"))
    )
    (comp (ref "S9")
      (value "PINHD-1X3")
      (footprint "eagle-import:1X03")
      (libsource (lib "eagle-import") (part "PINHD-1X3"))
    )
    (comp (ref "S10")
      (value "PINHD-1X3")
      (footprint "eagle-import:1X03")
      (libsource (lib "eagle-import") (part "PINHD-1X3"))
    )
    (comp (ref "S11")
      (value "PINHD-1X3")
      (footprint "eagle-import:1X03")
      (libsource (lib "eagle-import") (part "PINHD-1X3"))
    )
    (comp (ref "S12")
      (value "PINHD-1X3")
      (footprint "eagle-import:1X03")
      (libsource (lib "eagle-import") (part "PINHD-1X3"))
    )
    (comp (ref "S13")
      (value "PINHD-1X3")
      (footprint "eagle-import:1X03")
      (libsource (lib "eagle-import") (part "PINHD-1X3"))
    )
    (comp (ref "S14")
      (value "PINHD-1X3")
      (footprint "eagle-import:1X03")
      (libsource (lib "eagle-import") (part "PINHD-1X3"))
    )
    (comp (ref "S15")
      (value "PINHD-1X3")
      (footprint "eagle-import:1X03")
      (libsource (lib "eagle-import") (part "PINHD-1X3"))
    )
    (comp (ref "S16")
      (value "PINHD-1X3")
      (footprint "eagle-import:1X03")
      (libsource (lib "eagle-import") (part "PINHD-1X3"))
    )
    (comp (ref "S17")
      (value "PINHD-1X3")
      (footprint "eagle-import:1X03")
      (libsource (lib "eagle-import") (part "PINHD-1X3"))
    )
    (comp (ref "S18")
      (value "PINHD-1X3")
      (footprint "eagle-import:1X03")
      (libsource (lib "eagle-import") (part "PINHD-1X3"))
    )
    (comp (ref "S19")
      (value "PINHD-1X3")
      (footprint "eagle-import:1X03")
      (libsource (lib "eagle-import") (part "PINHD-1X3"))
    )
    (comp (ref "S20")
      (value "PINHD-1X3")
      (footprint "eagle-import:1X03")
      (libsource (lib "eagle-import") (part "PINHD-1X3"))
    )
    (comp (ref "S21")
      (value "PINHD-1X3")
      (footprint "eagle-import:1X03")
      (libsource (lib "eagle-import") (part "PINHD-1X3"))
    )
    (comp (ref "S22")
      (value "PINHD-1X3")
      (footprint "eagle-import:1X03")
      (libsource (lib "eagle-import") (part "PINHD-1X3"))
    )
    (comp (ref "S23")
      (value "PINHD-1X3")
      (footprint "eagle-import:1X03")
      (libsource (lib "eagle-import") (part "PINHD-1X3"))
    )
    (comp (ref "S24")
      (value "PINHD-1X3")
      (footprint "eagle-import:1X03")
      (libsource (lib "eagle-import") (part "PINHD-1X3"))
    )
    (comp (ref "S25")
      (value "PINHD-1X3")
      (footprint "eagle-import:1X03")
      (libsource (lib "eagle-import") (part "PINHD-1X3"))
    )
    (comp (ref "S26")
      (value "PINHD-1X3")
      (footprint "eagle-import:1X03")
      (libsource (lib "eagle-import") (part "PINHD-1X3"))
    )
    (comp (ref "S27")
      (value "PINHD-1X3")
      (footprint "eagle-import:1X03")
      (libsource (lib "eagle-import") (part "PINHD-1X3"))
    )
    (comp (ref "S28")
      (value "PINHD-1X3")
      (footprint "eagle-import:1X03")
      (libsource (lib "eagle-import") (part "PINHD-1X3"))
    )
    (comp (ref "S29")
      (value "PINHD-1X3")
      (footprint "eagle-import:1X03")
      (libsource (lib "eagle-import") (part "PINHD-1X3"))
    )
    (comp (ref "S30")
      (value "PINHD-1X3")
      (footprint "eagle-import:1X03")
      (libsource (lib "eagle-import") (part "PINHD-1X3"))
    )
    (comp (ref "S31")
      (value "PINHD-1X3")
      (footprint "eagle-import:1X03")
      (libsource (lib "eagle-import") (part "PINHD-1X3"))
    )
    (comp (ref "U$1")
      (value "MAX7317")
      (footprint "eagle-import:SOP63P600X175-16N")
      (libsource (lib "eagle-import") (part "MAX7317"))
    )
    (comp (ref "U$2")
      (value "TSR_1-2450")
      (footprint "eagle-import:TSR-1")
      (libsource (lib "eagle-import") (part "TSR_1-2450"))
    )
    (comp (ref "U$3")
      (value "TSR_1-2433")
      (footprint "eagle-import:TSR-1")
      (libsource (lib "eagle-import") (part "TSR_1-2433"))
    )
    (comp (ref "U$4")
      (value "STM32F429IDISCOVERY")
      (footprint "eagle-import:STM32F429IDISCOVERY")
      (libsource (lib "eagle-import") (part "STM32F429IDISCOVERY"))
    )
    (comp (ref "U$5")
      (value "MAX7317")
      (footprint "eagle-import:SOP63P600X175-16N")
      (libsource (lib "eagle-import") (part "MAX7317"))
    )
    (comp (ref "U1")
      (value "PCA9685")
      (footprint "eagle-import:TSSOP28")
      (libsource (lib "eagle-import") (part "PCA9685"))
    )
    (comp (ref "U2")
      (value "PCA9685")
      (footprint "eagle-import:TSSOP28")
      (libsource (lib "eagle-import") (part "PCA9685"))
    )
    (comp (ref "U3")
      (value "PCA9306")
      (footprint "eagle-import:PSOP-8")
      (libsource (lib "eagle-import") (part "PCA9306"))
    )
    (comp (ref "U4")
      (value "TXB0108PWR")
      (footprint "eagle-import:TSSOP20")
      (libsource (lib "eagle-import") (part "TXB0108PWR"))
    )
    (comp (ref "U5")
      (value "MAX11628EEE+")
      (footprint "eagle-import:SOP63P602X175-16N")
      (libsource (lib "eagle-import") (part "MAX11628EEE+"))
    )
    (comp (ref "U6")
      (value "MAX11628EEE+")
      (footprint "eagle-import:SOP63P602X175-16N")
      (libsource (lib "eagle-import") (part "MAX11628EEE+"))
    )
    (comp (ref "U7")
      (value "TXB0108PWR")
      (footprint "eagle-import:TSSOP20")
      (libsource (lib "eagle-import") (part "TXB0108PWR"))
    )
    (comp (ref "U8")
      (value "TXB0108PWR")
      (footprint "eagle-import:TSSOP20")
      (libsource (lib "eagle-import") (part "TXB0108PWR"))
    )
  )
  (nets
    (net (code "1") (name "+3V3") (class "Default")
      (node (ref "C44") (pin "1") (pinfunction "1_1") (pintype "passive"))
      (node (ref "C45") (pin "1") (pinfunction "1_1") (pintype "passive"))
      (node (ref "C47") (pin "1") (pinfunction "1_1") (pintype "passive"))
      (node (ref "C48") (pin "1") (pinfunction "1_1") (pintype "passive"))
      (node (ref "C5") (pin "1") (pinfunction "1_1") (pintype "passive"))
      (node (ref "C50") (pin "1") (pinfunction "1_1") (pintype "passive"))
      (node (ref "C9") (pin "1") (pinfunction "1_1") (pintype "passive"))
      (node (ref "C98") (pin "1") (pinfunction "1_1") (pintype "passive"))
      (node (ref "EC10") (pin "7") (pinfunction "7_7") (pintype "passive"))
      (node (ref "EC11") (pin "7") (pinfunction "7_7") (pintype "passive"))
      (node (ref "EC12") (pin "7") (pinfunction "7_7") (pintype "passive"))
      (node (ref "EC13") (pin "7") (pinfunction "7_7") (pintype "passive"))
      (node (ref "EC3") (pin "7") (pinfunction "7_7") (pintype "passive"))
      (node (ref "EC4") (pin "7") (pinfunction "7_7") (pintype "passive"))
      (node (ref "EC5") (pin "7") (pinfunction "7_7") (pintype "passive"))
      (node (ref "EC6") (pin "7") (pinfunction "7_7") (pintype "passive"))
      (node (ref "EC7") (pin "7") (pinfunction "7_7") (pintype "passive"))
      (node (ref "EC8") (pin "7") (pinfunction "7_7") (pintype "passive"))
      (node (ref "EC9") (pin "7") (pinfunction "7_7") (pintype "passive"))
      (node (ref "IC1") (pin "24") (pinfunction "VCC_24") (pintype "power_in"))
      (node (ref "IO0") (pin "2") (pinfunction "2_2") (pintype "passive"))
      (node (ref "IO1") (pin "2") (pinfunction "2_2") (pintype "passive"))
      (node (ref "IO18") (pin "2") (pinfunction "2_2") (pintype "passive"))
      (node (ref "IO19") (pin "2") (pinfunction "2_2") (pintype "passive"))
      (node (ref "IO2") (pin "2") (pinfunction "2_2") (pintype "passive"))
      (node (ref "IO3") (pin "2") (pinfunction "2_2") (pintype "passive"))
      (node (ref "IO4") (pin "2") (pinfunction "2_2") (pintype "passive"))
      (node (ref "IO5") (pin "2") (pinfunction "2_2") (pintype "passive"))
      (node (ref "IO6") (pin "2") (pinfunction "2_2") (pintype "passive"))
      (node (ref "IO7") (pin "2") (pinfunction "2_2") (pintype "passive"))
      (node (ref "IO8") (pin "2") (pinfunction "2_2") (pintype "passive"))
      (node (ref "IO9") (pin "2") (pinfunction "2_2") (pintype "passive"))
      (node (ref "JP2") (pin "2") (pinfunction "2_2") (pintype "passive"))
      (node (ref "M0") (pin "4") (pinfunction "4_4") (pintype "passive"))
      (node (ref "M1") (pin "4") (pinfunction "4_4") (pintype "passive"))
      (node (ref "R4") (pin "2") (pinfunction "2_2") (pintype "passive"))
      (node (ref "R5") (pin "2") (pinfunction "2_2") (pintype "passive"))
      (node (ref "U$1") (pin "16") (pinfunction "VCC_16") (pintype "bidirectional"))
      (node (ref "U$3") (pin "P$3") (pinfunction "VO_P$3") (pintype "bidirectional"))
      (node (ref "U$5") (pin "16") (pinfunction "VCC_16") (pintype "bidirectional"))
      (node (ref "U3") (pin "1") (pinfunction "VREF1_1") (pintype "bidirectional"))
      (node (ref "U4") (pin "10") (pinfunction "OE_10") (pintype "bidirectional"))
      (node (ref "U4") (pin "2") (pinfunction "VCCA_2") (pintype "bidirectional"))
      (node (ref "U7") (pin "10") (pinfunction "OE_10") (pintype "bidirectional"))
      (node (ref "U7") (pin "2") (pinfunction "VCCA_2") (pintype "bidirectional"))
      (node (ref "U8") (pin "10") (pinfunction "OE_10") (pintype "bidirectional"))
      (node (ref "U8") (pin "2") (pinfunction "VCCA_2") (pintype "bidirectional"))
    )
    (net (code "2") (name "+5V{slash}1") (class "Default")
      (node (ref "A0") (pin "1") (pinfunction "1_1") (pintype "passive"))
      (node (ref "A1") (pin "1") (pinfunction "1_1") (pintype "passive"))
      (node (ref "A10") (pin "1") (pinfunction "1_1") (pintype "passive"))
      (node (ref "A11") (pin "1") (pinfunction "1_1") (pintype "passive"))
      (node (ref "A12") (pin "1") (pinfunction "1_1") (pintype "passive"))
      (node (ref "A13") (pin "1") (pinfunction "1_1") (pintype "passive"))
      (node (ref "A14") (pin "1") (pinfunction "1_1") (pintype "passive"))
      (node (ref "A2") (pin "1") (pinfunction "1_1") (pintype "passive"))
      (node (ref "A3") (pin "1") (pinfunction "1_1") (pintype "passive"))
      (node (ref "A4") (pin "1") (pinfunction "1_1") (pintype "passive"))
      (node (ref "A5") (pin "1") (pinfunction "1_1") (pintype "passive"))
      (node (ref "A6") (pin "1") (pinfunction "1_1") (pintype "passive"))
      (node (ref "A7") (pin "1") (pinfunction "1_1") (pintype "passive"))
      (node (ref "A8") (pin "1") (pinfunction "1_1") (pintype "passive"))
      (node (ref "A9") (pin "1") (pinfunction "1_1") (pintype "passive"))
      (node (ref "C1") (pin "1") (pinfunction "1_1") (pintype "passive"))
      (node (ref "C10") (pin "1") (pinfunction "1_1") (pintype "passive"))
      (node (ref "C11") (pin "1") (pinfunction "1_1") (pintype "passive"))
      (node (ref "C14") (pin "1") (pinfunction "1_1") (pintype "passive"))
      (node (ref "C16") (pin "1") (pinfunction "1_1") (pintype "passive"))
      (node (ref "C18") (pin "1") (pinfunction "1_1") (pintype "passive"))
      (node (ref "C2") (pin "1") (pinfunction "1_1") (pintype "passive"))
      (node (ref "C20") (pin "1") (pinfunction "1_1") (pintype "passive"))
      (node (ref "C22") (pin "1") (pinfunction "1_1") (pintype "passive"))
      (node (ref "C24") (pin "1") (pinfunction "1_1") (pintype "passive"))
      (node (ref "C26") (pin "1") (pinfunction "1_1") (pintype "passive"))
      (node (ref "C28") (pin "1") (pinfunction "1_1") (pintype "passive"))
      (node (ref "C30") (pin "1") (pinfunction "1_1") (pintype "passive"))
      (node (ref "C32") (pin "1") (pinfunction "1_1") (pintype "passive"))
      (node (ref "C34") (pin "1") (pinfunction "1_1") (pintype "passive"))
      (node (ref "C36") (pin "1") (pinfunction "1_1") (pintype "passive"))
      (node (ref "C38") (pin "1") (pinfunction "1_1") (pintype "passive"))
      (node (ref "C40") (pin "1") (pinfunction "1_1") (pintype "passive"))
      (node (ref "C42") (pin "1") (pinfunction "1_1") (pintype "passive"))
      (node (ref "C46") (pin "1") (pinfunction "1_1") (pintype "passive"))
      (node (ref "C49") (pin "1") (pinfunction "1_1") (pintype "passive"))
      (node (ref "C6") (pin "1") (pinfunction "1_1") (pintype "passive"))
      (node (ref "C7") (pin "1") (pinfunction "1_1") (pintype "passive"))
      (node (ref "C95") (pin "1") (pinfunction "1_1") (pintype "passive"))
      (node (ref "C96") (pin "1") (pinfunction "1_1") (pintype "passive"))
      (node (ref "C97") (pin "1") (pinfunction "1_1") (pintype "passive"))
      (node (ref "EC10") (pin "8") (pinfunction "8_8") (pintype "passive"))
      (node (ref "EC11") (pin "8") (pinfunction "8_8") (pintype "passive"))
      (node (ref "EC12") (pin "8") (pinfunction "8_8") (pintype "passive"))
      (node (ref "EC13") (pin "8") (pinfunction "8_8") (pintype "passive"))
      (node (ref "EC3") (pin "8") (pinfunction "8_8") (pintype "passive"))
      (node (ref "EC4") (pin "8") (pinfunction "8_8") (pintype "passive"))
      (node (ref "EC5") (pin "8") (pinfunction "8_8") (pintype "passive"))
      (node (ref "EC6") (pin "8") (pinfunction "8_8") (pintype "passive"))
      (node (ref "EC7") (pin "8") (pinfunction "8_8") (pintype "passive"))
      (node (ref "EC8") (pin "8") (pinfunction "8_8") (pintype "passive"))
      (node (ref "EC9") (pin "8") (pinfunction "8_8") (pintype "passive"))
      (node (ref "ENC0") (pin "6") (pinfunction "6_6") (pintype "passive"))
      (node (ref "ENC1") (pin "6") (pinfunction "6_6") (pintype "passive"))
      (node (ref "GYRO") (pin "6") (pinfunction "6_6") (pintype "passive"))
      (node (ref "I2C") (pin "4") (pinfunction "4_4") (pintype "passive"))
      (node (ref "IO10") (pin "2") (pinfunction "2_2") (pintype "passive"))
      (node (ref "IO11") (pin "2") (pinfunction "2_2") (pintype "passive"))
      (node (ref "IO12") (pin "2") (pinfunction "2_2") (pintype "passive"))
      (node (ref "IO13") (pin "2") (pinfunction "2_2") (pintype "passive"))
      (node (ref "IO14") (pin "2") (pinfunction "2_2") (pintype "passive"))
      (node (ref "IO15") (pin "2") (pinfunction "2_2") (pintype "passive"))
      (node (ref "IO16") (pin "2") (pinfunction "2_2") (pintype "passive"))
      (node (ref "IO17") (pin "2") (pinfunction "2_2") (pintype "passive"))
      (node (ref "JP2") (pin "1") (pinfunction "1_1") (pintype "passive"))
      (node (ref "R1") (pin "2") (pinfunction "2_2") (pintype "passive"))
      (node (ref "R2") (pin "2") (pinfunction "2_2") (pintype "passive"))
      (node (ref "R3") (pin "2") (pinfunction "2_2") (pintype "passive"))
      (node (ref "S0") (pin "2") (pinfunction "2_2") (pintype "passive"))
      (node (ref "S1") (pin "2") (pinfunction "2_2") (pintype "passive"))
      (node (ref "S2") (pin "2") (pinfunction "2_2") (pintype "passive"))
      (node (ref "S3") (pin "2") (pinfunction "2_2") (pintype "passive"))
      (node (ref "U$2") (pin "P$3") (pinfunction "VO_P$3") (pintype "bidirectional"))
      (node (ref "U$4") (pin "P$1") (pinfunction "5V_1_P$1") (pintype "bidirectional"))
      (node (ref "U$4") (pin "P$2") (pinfunction "5V_2_P$2") (pintype "bidirectional"))
      (node (ref "U1") (pin "24") (pinfunction "A5_24") (pintype "bidirectional"))
      (node (ref "U1") (pin "28") (pinfunction "VDD_28") (pintype "power_in"))
      (node (ref "U1") (pin "5") (pinfunction "A4_5") (pintype "bidirectional"))
      (node (ref "U2") (pin "1") (pinfunction "A0_1") (pintype "bidirectional"))
      (node (ref "U2") (pin "24") (pinfunction "A5_24") (pintype "bidirectional"))
      (node (ref "U2") (pin "28") (pinfunction "VDD_28") (pintype "power_in"))
      (node (ref "U2") (pin "5") (pinfunction "A4_5") (pintype "bidirectional"))
      (node (ref "U4") (pin "19") (pinfunction "VCCB_19") (pintype "bidirectional"))
      (node (ref "U5") (pin "11") (pinfunction "VDD_11") (pintype "power_in"))
      (node (ref "U6") (pin "11") (pinfunction "VDD_11") (pintype "power_in"))
      (node (ref "U7") (pin "19") (pinfunction "VCCB_19") (pintype "bidirectional"))
      (node (ref "U8") (pin "19") (pinfunction "VCCB_19") (pintype "bidirectional"))
    )
    (net (code "3") (name "+5V{slash}2") (class "Default")
      (node (ref "5V/2") (pin "2") (pinfunction "2_2") (pintype "passive"))
      (node (ref "S4") (pin "2") (pinfunction "2_2") (pintype "passive"))
      (node (ref "S5") (pin "2") (pinfunction "2_2") (pintype "passive"))
      (node (ref "S6") (pin "2") (pinfunction "2_2") (pintype "passive"))
      (node (ref "S7") (pin "2") (pinfunction "2_2") (pintype "passive"))
    )
    (net (code "4") (name "+5V{slash}3") (class "Default")
      (node (ref "5V/3") (pin "2") (pinfunction "2_2") (pintype "passive"))
      (node (ref "S10") (pin "2") (pinfunction "2_2") (pintype "passive"))
      (node (ref "S11") (pin "2") (pinfunction "2_2") (pintype "passive"))
      (node (ref "S12") (pin "2") (pinfunction "2_2") (pintype "passive"))
      (node (ref "S13") (pin "2") (pinfunction "2_2") (pintype "passive"))
      (node (ref "S14") (pin "2") (pinfunction "2_2") (pintype "passive"))
      (node (ref "S15") (pin "2") (pinfunction "2_2") (pintype "passive"))
      (node (ref "S8") (pin "2") (pinfunction "2_2") (pintype "passive"))
      (node (ref "S9") (pin "2") (pinfunction "2_2") (pintype "passive"))
    )
    (net (code "5") (name "+5V{slash}4") (class "Default")
      (node (ref "5V/4") (pin "2") (pinfunction "2_2") (pintype "passive"))
      (node (ref "S16") (pin "2") (pinfunction "2_2") (pintype "passive"))
      (node (ref "S17") (pin "2") (pinfunction "2_2") (pintype "passive"))
      (node (ref "S18") (pin "2") (pinfunction "2_2") (pintype "passive"))
      (node (ref "S19") (pin "2") (pinfunction "2_2") (pintype "passive"))
      (node (ref "S20") (pin "2") (pinfunction "2_2") (pintype "passive"))
      (node (ref "S21") (pin "2") (pinfunction "2_2") (pintype "passive"))
      (node (ref "S22") (pin "2") (pinfunction "2_2") (pintype "passive"))
      (node (ref "S23") (pin "2") (pinfunction "2_2") (pintype "passive"))
      (node (ref "S24") (pin "2") (pinfunction "2_2") (pintype "passive"))
      (node (ref "S25") (pin "2") (pinfunction "2_2") (pintype "passive"))
      (node (ref "S26") (pin "2") (pinfunction "2_2") (pintype "passive"))
      (node (ref "S27") (pin "2") (pinfunction "2_2") (pintype "passive"))
      (node (ref "S28") (pin "2") (pinfunction "2_2") (pintype "passive"))
      (node (ref "S29") (pin "2") (pinfunction "2_2") (pintype "passive"))
      (node (ref "S30") (pin "2") (pinfunction "2_2") (pintype "passive"))
      (node (ref "S31") (pin "2") (pinfunction "2_2") (pintype "passive"))
    )
    (net (code "6") (name "/ADC_CH0") (class "Default")
      (node (ref "C13") (pin "1") (pinfunction "1_1") (pintype "passive"))
      (node (ref "R6") (pin "1") (pinfunction "1_1") (pintype "passive"))
      (node (ref "R7") (pin "1") (pinfunction "1_1") (pintype "passive"))
      (node (ref "U5") (pin "1") (pinfunction "AIN0_1") (pintype "input"))
    )
    (net (code "7") (name "/ADC_CH1") (class "Default")
      (node (ref "C15") (pin "1") (pinfunction "1_1") (pintype "passive"))
      (node (ref "R8") (pin "1") (pinfunction "1_1") (pintype "passive"))
      (node (ref "R9") (pin "1") (pinfunction "1_1") (pintype "passive"))
      (node (ref "U5") (pin "2") (pinfunction "AIN1_2") (pintype "input"))
    )
    (net (code "8") (name "/ADC_CH2") (class "Default")
      (node (ref "C17") (pin "1") (pinfunction "1_1") (pintype "passive"))
      (node (ref "R10") (pin "1") (pinfunction "1_1") (pintype "passive"))
      (node (ref "R11") (pin "1") (pinfunction "1_1") (pintype "passive"))
      (node (ref "U5") (pin "3") (pinfunction "AIN2_3") (pintype "input"))
    )
    (net (code "9") (name "/ADC_CH3") (class "Default")
      (node (ref "C37") (pin "1") (pinfunction "1_1") (pintype "passive"))
      (node (ref "R30") (pin "1") (pinfunction "1_1") (pintype "passive"))
      (node (ref "R31") (pin "1") (pinfunction "1_1") (pintype "passive"))
      (node (ref "U5") (pin "4") (pinfunction "AIN3_4") (pintype "input"))
    )
    (net (code "10") (name "/ADC_CH4") (class "Default")
      (node (ref "C19") (pin "1") (pinfunction "1_1") (pintype "passive"))
      (node (ref "R12") (pin "1") (pinfunction "1_1") (pintype "passive"))
      (node (ref "R13") (pin "1") (pinfunction "1_1") (pintype "passive"))
      (node (ref "U5") (pin "5") (pinfunction "AIN4_5") (pintype "input"))
    )
    (net (code "11") (name "/ADC_CH5") (class "Default")
      (node (ref "C21") (pin "1") (pinfunction "1_1") (pintype "passive"))
      (node (ref "R14") (pin "1") (pinfunction "1_1") (pintype "passive"))
      (node (ref "R15") (pin "1") (pinfunction "1_1") (pintype "passive"))
      (node (ref "U5") (pin "6") (pinfunction "AIN5_6") (pintype "input"))
    )
    (net (code "12") (name "/ADC_CH6") (class "Default")
      (node (ref "C23") (pin "1") (pinfunction "1_1") (pintype "passive"))
      (node (ref "R16") (pin "1") (pinfunction "1_1") (pintype "passive"))
      (node (ref "R17") (pin "1") (pinfunction "1_1") (pintype "passive"))
      (node (ref "U5") (pin "7") (pinfunction "AIN6_7") (pintype "input"))
    )
    (net (code "13") (name "/ADC_CH7") (class "Default")
      (node (ref "C39") (pin "1") (pinfunction "1_1") (pintype "passive"))
      (node (ref "R32") (pin "1") (pinfunction "1_1") (pintype "passive"))
      (node (ref "R33") (pin "1") (pinfunction "1_1") (pintype "passive"))
      (node (ref "U5") (pin "8") (pinfunction "AIN7_8") (pintype "input"))
    )
    (net (code "14") (name "/ADC_CH8") (class "Default")
      (node (ref "C25") (pin "1") (pinfunction "1_1") (pintype "passive"))
      (node (ref "R18") (pin "1") (pinfunction "1_1") (pintype "passive"))
      (node (ref "R19") (pin "1") (pinfunction "1_1") (pintype "passive"))
      (node (ref "U6") (pin "1") (pinfunction "AIN0_1") (pintype "input"))
    )
    (net (code "15") (name "/ADC_CH9") (class "Default")
      (node (ref "C27") (pin "1") (pinfunction "1_1") (pintype "passive"))
      (node (ref "R20") (pin "1") (pinfunction "1_1") (pintype "passive"))
      (node (ref "R21") (pin "1") (pinfunction "1_1") (pintype "passive"))
      (node (ref "U6") (pin "2") (pinfunction "AIN1_2") (pintype "input"))
    )
    (net (code "16") (name "/ADC_CH10") (class "Default")
      (node (ref "C29") (pin "1") (pinfunction "1_1") (pintype "passive"))
      (node (ref "R22") (pin "1") (pinfunction "1_1") (pintype "passive"))
      (node (ref "R23") (pin "1") (pinfunction "1_1") (pintype "passive"))
      (node (ref "U6") (pin "3") (pinfunction "AIN2_3") (pintype "input"))
    )
    (net (code "17") (name "/ADC_CH11") (class "Default")
      (node (ref "C41") (pin "1") (pinfunction "1_1") (pintype "passive"))
      (node (ref "R34") (pin "1") (pinfunction "1_1") (pintype "passive"))
      (node (ref "R35") (pin "1") (pinfunction "1_1") (pintype "passive"))
      (node (ref "U6") (pin "4") (pinfunction "AIN3_4") (pintype "input"))
    )
    (net (code "18") (name "/ADC_CH12") (class "Default")
      (node (ref "C31") (pin "1") (pinfunction "1_1") (pintype "passive"))
      (node (ref "R24") (pin "1") (pinfunction "1_1") (pintype "passive"))
      (node (ref "R25") (pin "1") (pinfunction "1_1") (pintype "passive"))
      (node (ref "U6") (pin "5") (pinfunction "AIN4_5") (pintype "input"))
    )
    (net (code "19") (name "/ADC_CH13") (class "Default")
      (node (ref "C33") (pin "1") (pinfunction "1_1") (pintype "passive"))
      (node (ref "R26") (pin "1") (pinfunction "1_1") (pintype "passive"))
      (node (ref "R27") (pin "1") (pinfunction "1_1") (pintype "passive"))
      (node (ref "U6") (pin "6") (pinfunction "AIN5_6") (pintype "input"))
    )
    (net (code "20") (name "/ADC_CH14") (class "Default")
      (node (ref "C35") (pin "1") (pinfunction "1_1") (pintype "passive"))
      (node (ref "R28") (pin "1") (pinfunction "1_1") (pintype "passive"))
      (node (ref "R29") (pin "1") (pinfunction "1_1") (pintype "passive"))
      (node (ref "U6") (pin "7") (pinfunction "AIN6_7") (pintype "input"))
    )
    (net (code "21") (name "/ADC_CH15") (class "Default")
      (node (ref "C43") (pin "1") (pinfunction "1_1") (pintype "passive"))
      (node (ref "R36") (pin "1") (pinfunction "1_1") (pintype "passive"))
      (node (ref "R37") (pin "1") (pinfunction "1_1") (pintype "passive"))
      (node (ref "U6") (pin "8") (pinfunction "AIN7_8") (pintype "input"))
    )
    (net (code "22") (name "/ALARM_3V3") (class "Default")
      (node (ref "JP2") (pin "3") (pinfunction "3_3") (pintype "passive"))
    )
    (net (code "23") (name "/ALRM0_3V3") (class "Default")
      (node (ref "U$4") (pin "P$25") (pinfunction "PB4_P$25") (pintype "bidirectional"))
    )
    (net (code "24") (name "/ALRM1_3V3") (class "Default")
      (node (ref "EC11") (pin "6") (pinfunction "6_6") (pintype "passive"))
      (node (ref "U$4") (pin "P$33") (pinfunction "PG9_P$33") (pintype "bidirectional"))
    )
    (net (code "25") (name "/ALRM2_3V3") (class "Default")
      (node (ref "EC12") (pin "6") (pinfunction "6_6") (pintype "passive"))
      (node (ref "U$4") (pin "P$35") (pinfunction "PD7_P$35") (pintype "bidirectional"))
    )
    (net (code "26") (name "/ALRM3_3V3") (class "Default")
      (node (ref "EC13") (pin "6") (pinfunction "6_6") (pintype "passive"))
      (node (ref "U$4") (pin "P$37") (pinfunction "PD5_P$37") (pintype "bidirectional"))
    )
    (net (code "27") (name "/CS_3_3V3") (class "Default")
      (node (ref "IC1") (pin "4") (pinfunction "3_4") (pintype "output"))
      (node (ref "U7") (pin "7") (pinfunction "A6_7") (pintype "bidirectional"))
    )
    (net (code "28") (name "/CS_3_5V") (class "Default")
      (node (ref "EC3") (pin "2") (pinfunction "2_2") (pintype "passive"))
      (node (ref "U7") (pin "14") (pinfunction "B6_14") (pintype "bidirectional"))
    )
    (net (code "29") (name "/CS_4_3V3") (class "Default")
      (node (ref "IC1") (pin "5") (pinfunction "4_5") (pintype "output"))
      (node (ref "U7") (pin "8") (pinfunction "A7_8") (pintype "bidirectional"))
    )
    (net (code "30") (name "/CS_4_5V") (class "Default")
      (node (ref "EC4") (pin "2") (pinfunction "2_2") (pintype "passive"))
      (node (ref "U7") (pin "13") (pinfunction "B7_13") (pintype "bidirectional"))
    )
    (net (code "31") (name "/CS_5_3V3") (class "Default")
      (node (ref "IC1") (pin "6") (pinfunction "5_6") (pintype "output"))
      (node (ref "U7") (pin "9") (pinfunction "A8_9") (pintype "bidirectional"))
    )
    (net (code "32") (name "/CS_5_5V") (class "Default")
      (node (ref "EC5") (pin "2") (pinfunction "2_2") (pintype "passive"))
      (node (ref "U7") (pin "12") (pinfunction "B8_12") (pintype "bidirectional"))
    )
    (net (code "33") (name "/CS_6_3V3") (class "Default")
      (node (ref "EC6") (pin "2") (pinfunction "2_2") (pintype "passive"))
      (node (ref "IC1") (pin "7") (pinfunction "6_7") (pintype "output"))
    )
    (net (code "34") (name "/CS_7_3V3") (class "Default")
      (node (ref "EC7") (pin "2") (pinfunction "2_2") (pintype "passive"))
      (node (ref "IC1") (pin "8") (pinfunction "7_8") (pintype "output"))
    )
    (net (code "35") (name "/CS_8_3V3") (class "Default")
      (node (ref "EC8") (pin "2") (pinfunction "2_2") (pintype "passive"))
      (node (ref "IC1") (pin "9") (pinfunction "8_9") (pintype "output"))
    )
    (net (code "36") (name "/CS_9_3V3") (class "Default")
      (node (ref "EC9") (pin "2") (pinfunction "2_2") (pintype "passive"))
      (node (ref "IC1") (pin "10") (pinfunction "9_10") (pintype "output"))
    )
    (net (code "37") (name "/CS_10_3V3") (class "Default")
      (node (ref "EC10") (pin "2") (pinfunction "2_2") (pintype "passive"))
      (node (ref "IC1") (pin "11") (pinfunction "10_11") (pintype "output"))
    )
    (net (code "38") (name "/CS_11_3V3") (class "Default")
      (node (ref "EC11") (pin "2") (pinfunction "2_2") (pintype "passive"))
      (node (ref "IC1") (pin "13") (pinfunction "11_13") (pintype "output"))
    )
    (net (code "39") (name "/CS_12_3V3") (class "Default")
      (node (ref "EC12") (pin "2") (pinfunction "2_2") (pintype "passive"))
      (node (ref "IC1") (pin "14") (pinfunction "12_14") (pintype "output"))
    )
    (net (code "40") (name "/CS_13_3V3") (class "Default")
      (node (ref "EC13") (pin "2") (pinfunction "2_2") (pintype "passive"))
      (node (ref "IC1") (pin "15") (pinfunction "13_15") (pintype "output"))
    )
    (net (code "41") (name "/CS_ADC0_3V3") (class "Default")
      (node (ref "IC1") (pin "2") (pinfunction "1_2") (pintype "output"))
      (node (ref "U7") (pin "5") (pinfunction "A4_5") (pintype "bidirectional"))
    )
    (net (code "42") (name "/CS_ADC0_5V") (class "Default")
      (node (ref "U5") (pin "12") (pinfunction "~{CS}_12") (pintype "input"))
      (node (ref "U7") (pin "16") (pinfunction "B4_16") (pintype "bidirectional"))
    )
    (net (code "43") (name "/CS_ADC1_3V3") (class "Default")
      (node (ref "IC1") (pin "3") (pinfunction "2_3") (pintype "output"))
      (node (ref "U7") (pin "6") (pinfunction "A5_6") (pintype "bidirectional"))
    )
    (net (code "44") (name "/CS_ADC1_5V") (class "Default")
      (node (ref "U6") (pin "12") (pinfunction "~{CS}_12") (pintype "input"))
      (node (ref "U7") (pin "15") (pinfunction "B5_15") (pintype "bidirectional"))
    )
    (net (code "45") (name "/CS_ENC0_3V3") (class "Default")
      (node (ref "U$4") (pin "P$16") (pinfunction "PE3_P$16") (pintype "bidirectional"))
      (node (ref "U4") (pin "5") (pinfunction "A4_5") (pintype "bidirectional"))
    )
    (net (code "46") (name "/CS_ENC0_5V") (class "Default")
      (node (ref "ENC0") (pin "2") (pinfunction "2_2") (pintype "passive"))
      (node (ref "U4") (pin "16") (pinfunction "B4_16") (pintype "bidirectional"))
    )
    (net (code "47") (name "/CS_ENC1_3V3") (class "Default")
      (node (ref "U$4") (pin "P$12") (pinfunction "PC13_P$12") (pintype "bidirectional"))
      (node (ref "U4") (pin "6") (pinfunction "A5_6") (pintype "bidirectional"))
    )
    (net (code "48") (name "/CS_ENC1_5V") (class "Default")
      (node (ref "ENC1") (pin "2") (pinfunction "2_2") (pintype "passive"))
      (node (ref "U4") (pin "15") (pinfunction "B5_15") (pintype "bidirectional"))
    )
    (net (code "49") (name "/CS_EXT0_3V3") (class "Default")
      (node (ref "U4") (pin "8") (pinfunction "A7_8") (pintype "bidirectional"))
    )
    (net (code "50") (name "/CS_EXT0_5V") (class "Default")
      (node (ref "U4") (pin "13") (pinfunction "B7_13") (pintype "bidirectional"))
    )
    (net (code "51") (name "/CS_EXT1_3V3") (class "Default")
      (node (ref "U4") (pin "9") (pinfunction "A8_9") (pintype "bidirectional"))
    )
    (net (code "52") (name "/CS_EXT1_5V") (class "Default")
      (node (ref "U4") (pin "12") (pinfunction "B8_12") (pintype "bidirectional"))
    )
    (net (code "53") (name "/CS_GYRO_3V3") (class "Default")
      (node (ref "U$4") (pin "P$13") (pinfunction "PE4_P$13") (pintype "bidirectional"))
      (node (ref "U4") (pin "7") (pinfunction "A6_7") (pintype "bidirectional"))
    )
    (net (code "54") (name "/CS_GYRO_5V") (class "Default")
      (node (ref "GYRO") (pin "2") (pinfunction "2_2") (pintype "passive"))
      (node (ref "U4") (pin "14") (pinfunction "B6_14") (pintype "bidirectional"))
    )
    (net (code "55") (name "/CS_IOE0_3V3") (class "Default")
      (node (ref "IC1") (pin "16") (pinfunction "14_16") (pintype "output"))
      (node (ref "U$1") (pin "2") (pinfunction "/CS_2") (pintype "bidirectional"))
    )
    (net (code "56") (name "/CS_IOE1_3V3") (class "Default")
      (node (ref "IC1") (pin "17") (pinfunction "15_17") (pintype "output"))
      (node (ref "U$5") (pin "2") (pinfunction "/CS_2") (pintype "bidirectional"))
    )
    (net (code "57") (name "/CS_SEL0_3V3") (class "Default")
      (node (ref "IC1") (pin "23") (pinfunction "A_23") (pintype "input"))
      (node (ref "U$4") (pin "P$126") (pinfunction "PG2_P$126") (pintype "bidirectional"))
    )
    (net (code "58") (name "/CS_SEL1_3V3") (class "Default")
      (node (ref "IC1") (pin "22") (pinfunction "B_22") (pintype "input"))
      (node (ref "U$4") (pin "P$125") (pinfunction "PG3_P$125") (pintype "bidirectional"))
    )
    (net (code "59") (name "/CS_SEL2_3V3") (class "Default")
      (node (ref "IC1") (pin "21") (pinfunction "C_21") (pintype "input"))
      (node (ref "U$4") (pin "P$67") (pinfunction "PF6_P$67") (pintype "bidirectional"))
    )
    (net (code "60") (name "/CS_SEL3_3V3") (class "Default")
      (node (ref "IC1") (pin "20") (pinfunction "D_20") (pintype "input"))
      (node (ref "U$4") (pin "P$55") (pinfunction "PC8_P$55") (pintype "bidirectional"))
    )
    (net (code "61") (name "/ERR_M0_3V3") (class "Default")
      (node (ref "M0") (pin "2") (pinfunction "2_2") (pintype "passive"))
      (node (ref "U$4") (pin "P$40") (pinfunction "PD2_P$40") (pintype "bidirectional"))
    )
    (net (code "62") (name "/ERR_M1_3V3") (class "Default")
      (node (ref "M1") (pin "2") (pinfunction "2_2") (pintype "passive"))
      (node (ref "U$4") (pin "P$38") (pinfunction "PD4_P$38") (pintype "bidirectional"))
    )
    (net (code "63") (name "/I2C3_SCL_3V3") (class "Default")
      (node (ref "R5") (pin "1") (pinfunction "1_1") (pintype "passive"))
      (node (ref "U$4") (pin "P$53") (pinfunction "PA8_P$53") (pintype "bidirectional"))
      (node (ref "U3") (pin "2") (pinfunction "SCL1_2") (pintype "bidirectional"))
    )
    (net (code "64") (name "/I2C3_SDA_3V3") (class "Default")
      (node (ref "R4") (pin "1") (pinfunction "1_1") (pintype "passive"))
      (node (ref "U$4") (pin "P$54") (pinfunction "PC9_P$54") (pintype "bidirectional"))
      (node (ref "U3") (pin "3") (pinfunction "SDA1_3") (pintype "bidirectional"))
    )
    (net (code "65") (name "/IO0_3V3") (class "Default")
      (node (ref "IO0") (pin "1") (pinfunction "1_1") (pintype "passive"))
      (node (ref "U$1") (pin "3") (pinfunction "P0_3") (pintype "bidirectional"))
    )
    (net (code "66") (name "/IO1_3V3") (class "Default")
      (node (ref "IO1") (pin "1") (pinfunction "1_1") (pintype "passive"))
      (node (ref "U$1") (pin "4") (pinfunction "P1_4") (pintype "bidirectional"))
    )
    (net (code "67") (name "/IO2_3V3") (class "Default")
      (node (ref "IO2") (pin "1") (pinfunction "1_1") (pintype "passive"))
      (node (ref "U$1") (pin "5") (pinfunction "P2_5") (pintype "bidirectional"))
    )
    (net (code "68") (name "/IO3_3V3") (class "Default")
      (node (ref "IO3") (pin "1") (pinfunction "1_1") (pintype "passive"))
      (node (ref "U$1") (pin "6") (pinfunction "P3_6") (pintype "bidirectional"))
    )
    (net (code "69") (name "/IO4_3V3") (class "Default")
      (node (ref "IO4") (pin "1") (pinfunction "1_1") (pintype "passive"))
      (node (ref "U$1") (pin "7") (pinfunction "P4_7") (pintype "bidirectional"))
    )
    (net (code "70") (name "/IO5_3V3") (class "Default")
      (node (ref "IO5") (pin "1") (pinfunction "1_1") (pintype "passive"))
      (node (ref "U$1") (pin "9") (pinfunction "P5_9") (pintype "bidirectional"))
    )
    (net (code "71") (name "/IO6_3V3") (class "Default")
      (node (ref "IO6") (pin "1") (pinfunction "1_1") (pintype "passive"))
      (node (ref "U$1") (pin "10") (pinfunction "P6_10") (pintype "bidirectional"))
    )
    (net (code "72") (name "/IO7_3V3") (class "Default")
      (node (ref "IO7") (pin "1") (pinfunction "1_1") (pintype "passive"))
      (node (ref "U$1") (pin "11") (pinfunction "P7_11") (pintype "bidirectional"))
    )
    (net (code "73") (name "/IO8_3V3") (class "Default")
      (node (ref "IO8") (pin "1") (pinfunction "1_1") (pintype "passive"))
      (node (ref "U$1") (pin "12") (pinfunction "P8_12") (pintype "bidirectional"))
    )
    (net (code "74") (name "/IO9_3V3") (class "Default")
      (node (ref "IO9") (pin "1") (pinfunction "1_1") (pintype "passive"))
      (node (ref "U$1") (pin "13") (pinfunction "P9_13") (pintype "bidirectional"))
    )
    (net (code "75") (name "/IO10_5V") (class "Default")
      (node (ref "IO10") (pin "1") (pinfunction "1_1") (pintype "passive"))
      (node (ref "U8") (pin "20") (pinfunction "B1_20") (pintype "bidirectional"))
    )
    (net (code "76") (name "/IO11_5V") (class "Default")
      (node (ref "IO11") (pin "1") (pinfunction "1_1") (pintype "passive"))
      (node (ref "U8") (pin "18") (pinfunction "B2_18") (pintype "bidirectional"))
    )
    (net (code "77") (name "/IO12_5V") (class "Default")
      (node (ref "IO12") (pin "1") (pinfunction "1_1") (pintype "passive"))
      (node (ref "U8") (pin "17") (pinfunction "B3_17") (pintype "bidirectional"))
    )
    (net (code "78") (name "/IO13_5V") (class "Default")
      (node (ref "IO13") (pin "1") (pinfunction "1_1") (pintype "passive"))
      (node (ref "U8") (pin "16") (pinfunction "B4_16") (pintype "bidirectional"))
    )
    (net (code "79") (name "/IO14_5V") (class "Default")
      (node (ref "IO14") (pin "1") (pinfunction "1_1") (pintype "passive"))
      (node (ref "U8") (pin "15") (pinfunction "B5_15") (pintype "bidirectional"))
    )
    (net (code "80") (name "/IO15_5V") (class "Default")
      (node (ref "IO15") (pin "1") (pinfunction "1_1") (pintype "passive"))
      (node (ref "U8") (pin "14") (pinfunction "B6_14") (pintype "bidirectional"))
    )
    (net (code "81") (name "/IO16_5V") (class "Default")
      (node (ref "IO16") (pin "1") (pinfunction "1_1") (pintype "passive"))
      (node (ref "U8") (pin "13") (pinfunction "B7_13") (pintype "bidirectional"))
    )
    (net (code "82") (name "/IO17_5V") (class "Default")
      (node (ref "IO17") (pin "1") (pinfunction "1_1") (pintype "passive"))
      (node (ref "U8") (pin "12") (pinfunction "B8_12") (pintype "bidirectional"))
    )
    (net (code "83") (name "/IO18_3V3") (class "Default")
      (node (ref "IO18") (pin "1") (pinfunction "1_1") (pintype "passive"))
      (node (ref "U$5") (pin "12") (pinfunction "P8_12") (pintype "bidirectional"))
    )
    (net (code "84") (name "/IO19_3V3") (class "Default")
      (node (ref "IO19") (pin "1") (pinfunction "1_1") (pintype "passive"))
      (node (ref "U$5") (pin "13") (pinfunction "P9_13") (pintype "bidirectional"))
    )
    (net (code "85") (name "/PWM_M0_3V3") (class "Default")
      (node (ref "M0") (pin "6") (pinfunction "6_6") (pintype "passive"))
      (node (ref "U$4") (pin "P$85") (pinfunction "PA5_P$85") (pintype "bidirectional"))
    )
    (net (code "86") (name "/PWM_M1_3V3") (class "Default")
      (node (ref "M1") (pin "6") (pinfunction "6_6") (pintype "passive"))
      (node (ref "U$4") (pin "P$51") (pinfunction "PA10_P$51") (pintype "bidirectional"))
    )
    (net (code "87") (name "/RST_M_3V3") (class "Default")
      (node (ref "M0") (pin "3") (pinfunction "3_3") (pintype "passive"))
      (node (ref "M1") (pin "3") (pinfunction "3_3") (pintype "passive"))
      (node (ref "U$4") (pin "P$79") (pinfunction "PC3_P$79") (pintype "bidirectional"))
    )
    (net (code "88") (name "/SCL_5V") (class "Default")
      (node (ref "I2C") (pin "3") (pinfunction "3_3") (pintype "passive"))
      (node (ref "R2") (pin "1") (pinfunction "1_1") (pintype "passive"))
      (node (ref "U1") (pin "26") (pinfunction "SCL_26") (pintype "bidirectional"))
      (node (ref "U2") (pin "26") (pinfunction "SCL_26") (pintype "bidirectional"))
      (node (ref "U3") (pin "6") (pinfunction "SCL2_6") (pintype "bidirectional"))
    )
    (net (code "89") (name "/SDA_5V") (class "Default")
      (node (ref "I2C") (pin "2") (pinfunction "2_2") (pintype "passive"))
      (node (ref "R3") (pin "1") (pinfunction "1_1") (pintype "passive"))
      (node (ref "U1") (pin "27") (pinfunction "SDA_27") (pintype "bidirectional"))
      (node (ref "U2") (pin "27") (pinfunction "SDA_27") (pintype "bidirectional"))
      (node (ref "U3") (pin "5") (pinfunction "SDA2_5") (pintype "bidirectional"))
    )
    (net (code "90") (name "/SERVO0_5V") (class "Default")
      (node (ref "S0") (pin "1") (pinfunction "1_1") (pintype "passive"))
      (node (ref "U1") (pin "6") (pinfunction "PWM0_6") (pintype "output"))
    )
    (net (code "91") (name "/SERVO1_5V") (class "Default")
      (node (ref "S1") (pin "1") (pinfunction "1_1") (pintype "passive"))
      (node (ref "U1") (pin "7") (pinfunction "PWM1_7") (pintype "output"))
    )
    (net (code "92") (name "/SERVO2_5V") (class "Default")
      (node (ref "S2") (pin "1") (pinfunction "1_1") (pintype "passive"))
      (node (ref "U1") (pin "8") (pinfunction "PWM2_8") (pintype "output"))
    )
    (net (code "93") (name "/SERVO3_5V") (class "Default")
      (node (ref "S3") (pin "1") (pinfunction "1_1") (pintype "passive"))
      (node (ref "U1") (pin "9") (pinfunction "PWM3_9") (pintype "output"))
    )
    (net (code "94") (name "/SERVO4_5V") (class "Default")
      (node (ref "S4") (pin "1") (pinfunction "1_1") (pintype "passive"))
      (node (ref "U1") (pin "10") (pinfunction "PWM4_10") (pintype "output"))
    )
    (net (code "95") (name "/SERVO5_5V") (class "Default")
      (node (ref "S5") (pin "1") (pinfunction "1_1") (pintype "passive"))
      (node (ref "U1") (pin "11") (pinfunction "PWM5_11") (pintype "output"))
    )
    (net (code "96") (name "/SERVO6_5V") (class "Default")
      (node (ref "S6") (pin "1") (pinfunction "1_1") (pintype "passive"))
      (node (ref "U1") (pin "12") (pinfunction "PWM6_12") (pintype "output"))
    )
    (net (code "97") (name "/SERVO7_5V") (class "Default")
      (node (ref "S7") (pin "1") (pinfunction "1_1") (pintype "passive"))
      (node (ref "U1") (pin "13") (pinfunction "PWM7_13") (pintype "output"))
    )
    (net (code "98") (name "/SERVO8_5V") (class "Default")
      (node (ref "S8") (pin "1") (pinfunction "1_1") (pintype "passive"))
      (node (ref "U1") (pin "15") (pinfunction "PWM8_15") (pintype "output"))
    )
    (net (code "99") (name "/SERVO9_5V") (class "Default")
      (node (ref "S9") (pin "1") (pinfunction "1_1") (pintype "passive"))
      (node (ref "U1") (pin "16") (pinfunction "PWM9_16") (pintype "output"))
    )
    (net (code "100") (name "/SERVO10_5V") (class "Default")
      (node (ref "S10") (pin "1") (pinfunction "1_1") (pintype "passive"))
      (node (ref "U1") (pin "17") (pinfunction "PWM10_17") (pintype "output"))
    )
    (net (code "101") (name "/SERVO11_5V") (class "Default")
      (node (ref "S11") (pin "1") (pinfunction "1_1") (pintype "passive"))
      (node (ref "U1") (pin "18") (pinfunction "PWM11_18") (pintype "output"))
    )
    (net (code "102") (name "/SERVO12_5V") (class "Default")
      (node (ref "S12") (pin "1") (pinfunction "1_1") (pintype "passive"))
      (node (ref "U1") (pin "19") (pinfunction "PWM12_19") (pintype "output"))
    )
    (net (code "103") (name "/SERVO13_5V") (class "Default")
      (node (ref "S13") (pin "1") (pinfunction "1_1") (pintype "passive"))
      (node (ref "U1") (pin "20") (pinfunction "PWM13_20") (pintype "output"))
    )
    (net (code "104") (name "/SERVO14_5V") (class "Default")
      (node (ref "S14") (pin "1") (pinfunction "1_1") (pintype "passive"))
      (node (ref "U1") (pin "21") (pinfunction "PWM14_21") (pintype "output"))
    )
    (net (code "105") (name "/SERVO15_5V") (class "Default")
      (node (ref "S15") (pin "1") (pinfunction "1_1") (pintype "passive"))
      (node (ref "U1") (pin "22") (pinfunction "PWM15_22") (pintype "output"))
    )
    (net (code "106") (name "/SERVO16_5V") (class "Default")
      (node (ref "S16") (pin "1") (pinfunction "1_1") (pintype "passive"))
      (node (ref "U2") (pin "6") (pinfunction "PWM0_6") (pintype "output"))
    )
    (net (code "107") (name "/SERVO17_5V") (class "Default")
      (node (ref "S17") (pin "1") (pinfunction "1_1") (pintype "passive"))
      (node (ref "U2") (pin "7") (pinfunction "PWM1_7") (pintype "output"))
    )
    (net (code "108") (name "/SERVO18_5V") (class "Default")
      (node (ref "S18") (pin "1") (pinfunction "1_1") (pintype "passive"))
      (node (ref "U2") (pin "8") (pinfunction "PWM2_8") (pintype "output"))
    )
    (net (code "109") (name "/SERVO19_5V") (class "Default")
      (node (ref "S19") (pin "1") (pinfunction "1_1") (pintype "passive"))
      (node (ref "U2") (pin "9") (pinfunction "PWM3_9") (pintype "output"))
    )
    (net (code "110") (name "/SERVO20_5V") (class "Default")
      (node (ref "S20") (pin "1") (pinfunction "1_1") (pintype "passive"))
      (node (ref "U2") (pin "10") (pinfunction "PWM4_10") (pintype "output"))
    )
    (net (code "111") (name "/SERVO21_5V") (class "Default")
      (node (ref "S21") (pin "1") (pinfunction "1_1") (pintype "passive"))
      (node (ref "U2") (pin "11") (pinfunction "PWM5_11") (pintype "output"))
    )
    (net (code "112") (name "/SERVO22_5V") (class "Default")
      (node (ref "S22") (pin "1") (pinfunction "1_1") (pintype "passive"))
      (node (ref "U2") (pin "12") (pinfunction "PWM6_12") (pintype "output"))
    )
    (net (code "113") (name "/SERVO23_5V") (class "Default")
      (node (ref "S23") (pin "1") (pinfunction "1_1") (pintype "passive"))
      (node (ref "U2") (pin "13") (pinfunction "PWM7_13") (pintype "output"))
    )
    (net (code "114") (name "/SERVO24_5V") (class "Default")
      (node (ref "S24") (pin "1") (pinfunction "1_1") (pintype "passive"))
      (node (ref "U2") (pin "15") (pinfunction "PWM8_15") (pintype "output"))
    )
    (net (code "115") (name "/SERVO25_5V") (class "Default")
      (node (ref "S25") (pin "1") (pinfunction "1_1") (pintype "passive"))
      (node (ref "U2") (pin "16") (pinfunction "PWM9_16") (pintype "output"))
    )
    (net (code "116") (name "/SERVO26_5V") (class "Default")
      (node (ref "S26") (pin "1") (pinfunction "1_1") (pintype "passive"))
      (node (ref "U2") (pin "17") (pinfunction "PWM10_17") (pintype "output"))
    )
    (net (code "117") (name "/SERVO27_5V") (class "Default")
      (node (ref "S27") (pin "1") (pinfunction "1_1") (pintype "passive"))
      (node (ref "U2") (pin "18") (pinfunction "PWM11_18") (pintype "output"))
    )
    (net (code "118") (name "/SERVO28_5V") (class "Default")
      (node (ref "S28") (pin "1") (pinfunction "1_1") (pintype "passive"))
      (node (ref "U2") (pin "19") (pinfunction "PWM12_19") (pintype "output"))
    )
    (net (code "119") (name "/SERVO29_5V") (class "Default")
      (node (ref "S29") (pin "1") (pinfunction "1_1") (pintype "passive"))
      (node (ref "U2") (pin "20") (pinfunction "PWM13_20") (pintype "output"))
    )
    (net (code "120") (name "/SERVO30_5V") (class "Default")
      (node (ref "S30") (pin "1") (pinfunction "1_1") (pintype "passive"))
      (node (ref "U2") (pin "21") (pinfunction "PWM14_21") (pintype "output"))
    )
    (net (code "121") (name "/SERVO31_5V") (class "Default")
      (node (ref "S31") (pin "1") (pinfunction "1_1") (pintype "passive"))
      (node (ref "U2") (pin "22") (pinfunction "PWM15_22") (pintype "output"))
    )
    (net (code "122") (name "/SNS_M0_3V3") (class "Default")
      (node (ref "M0") (pin "5") (pinfunction "5_5") (pintype "passive"))
      (node (ref "U$4") (pin "P$44") (pinfunction "PC11_P$44") (pintype "bidirectional"))
    )
    (net (code "123") (name "/SNS_M1_3V3") (class "Default")
      (node (ref "M1") (pin "5") (pinfunction "5_5") (pintype "passive"))
      (node (ref "U$4") (pin "P$43") (pinfunction "PC12_P$43") (pintype "bidirectional"))
    )
    (net (code "124") (name "/SPI4_MISO_3V3") (class "Default")
      (node (ref "U$4") (pin "P$14") (pinfunction "PE5_P$14") (pintype "bidirectional"))
      (node (ref "U4") (pin "3") (pinfunction "A2_3") (pintype "bidirectional"))
    )
    (net (code "125") (name "/SPI4_MISO_5V") (class "Default")
      (node (ref "ENC0") (pin "4") (pinfunction "4_4") (pintype "passive"))
      (node (ref "ENC1") (pin "4") (pinfunction "4_4") (pintype "passive"))
      (node (ref "GYRO") (pin "4") (pinfunction "4_4") (pintype "passive"))
      (node (ref "U4") (pin "18") (pinfunction "B2_18") (pintype "bidirectional"))
    )
    (net (code "126") (name "/SPI4_MOSI_3V3") (class "Default")
      (node (ref "U$4") (pin "P$11") (pinfunction "PE6_P$11") (pintype "bidirectional"))
      (node (ref "U4") (pin "1") (pinfunction "A1_1") (pintype "bidirectional"))
    )
    (net (code "127") (name "/SPI4_MOSI_5V") (class "Default")
      (node (ref "ENC0") (pin "5") (pinfunction "5_5") (pintype "passive"))
      (node (ref "ENC1") (pin "5") (pinfunction "5_5") (pintype "passive"))
      (node (ref "GYRO") (pin "5") (pinfunction "5_5") (pintype "passive"))
      (node (ref "U4") (pin "20") (pinfunction "B1_20") (pintype "bidirectional"))
    )
    (net (code "128") (name "/SPI4_SCK_3V3") (class "Default")
      (node (ref "U$4") (pin "P$15") (pinfunction "PE2_P$15") (pintype "bidirectional"))
      (node (ref "U4") (pin "4") (pinfunction "A3_4") (pintype "bidirectional"))
    )
    (net (code "129") (name "/SPI4_SCK_5V") (class "Default")
      (node (ref "ENC0") (pin "3") (pinfunction "3_3") (pintype "passive"))
      (node (ref "ENC1") (pin "3") (pinfunction "3_3") (pintype "passive"))
      (node (ref "GYRO") (pin "3") (pinfunction "3_3") (pintype "passive"))
      (node (ref "U4") (pin "17") (pinfunction "B3_17") (pintype "bidirectional"))
    )
    (net (code "130") (name "/SPI5_MISO_3V3") (class "Default")
      (node (ref "EC10") (pin "4") (pinfunction "4_4") (pintype "passive"))
      (node (ref "EC11") (pin "4") (pinfunction "4_4") (pintype "passive"))
      (node (ref "EC12") (pin "4") (pinfunction "4_4") (pintype "passive"))
      (node (ref "EC13") (pin "4") (pinfunction "4_4") (pintype "passive"))
      (node (ref "EC6") (pin "4") (pinfunction "4_4") (pintype "passive"))
      (node (ref "EC7") (pin "4") (pinfunction "4_4") (pintype "passive"))
      (node (ref "EC8") (pin "4") (pinfunction "4_4") (pintype "passive"))
      (node (ref "EC9") (pin "4") (pinfunction "4_4") (pintype "passive"))
      (node (ref "U$1") (pin "14") (pinfunction "DOUT_14") (pintype "bidirectional"))
      (node (ref "U$4") (pin "P$69") (pinfunction "PF8_P$69") (pintype "bidirectional"))
      (node (ref "U$5") (pin "14") (pinfunction "DOUT_14") (pintype "bidirectional"))
      (node (ref "U7") (pin "3") (pinfunction "A2_3") (pintype "bidirectional"))
    )
    (net (code "131") (name "/SPI5_MISO_5V") (class "Default")
      (node (ref "EC3") (pin "4") (pinfunction "4_4") (pintype "passive"))
      (node (ref "EC4") (pin "4") (pinfunction "4_4") (pintype "passive"))
      (node (ref "EC5") (pin "4") (pinfunction "4_4") (pintype "passive"))
      (node (ref "U5") (pin "15") (pinfunction "DOUT_15") (pintype "output"))
      (node (ref "U6") (pin "15") (pinfunction "DOUT_15") (pintype "output"))
      (node (ref "U7") (pin "18") (pinfunction "B2_18") (pintype "bidirectional"))
    )
    (net (code "132") (name "/SPI5_MOSI_3V3") (class "Default")
      (node (ref "EC10") (pin "5") (pinfunction "5_5") (pintype "passive"))
      (node (ref "EC11") (pin "5") (pinfunction "5_5") (pintype "passive"))
      (node (ref "EC12") (pin "5") (pinfunction "5_5") (pintype "passive"))
      (node (ref "EC13") (pin "5") (pinfunction "5_5") (pintype "passive"))
      (node (ref "EC6") (pin "5") (pinfunction "5_5") (pintype "passive"))
      (node (ref "EC7") (pin "5") (pinfunction "5_5") (pintype "passive"))
      (node (ref "EC8") (pin "5") (pinfunction "5_5") (pintype "passive"))
      (node (ref "EC9") (pin "5") (pinfunction "5_5") (pintype "passive"))
      (node (ref "U$1") (pin "15") (pinfunction "DIN_15") (pintype "bidirectional"))
      (node (ref "U$4") (pin "P$72") (pinfunction "PF9_P$72") (pintype "bidirectional"))
      (node (ref "U$5") (pin "15") (pinfunction "DIN_15") (pintype "bidirectional"))
      (node (ref "U7") (pin "1") (pinfunction "A1_1") (pintype "bidirectional"))
    )
    (net (code "133") (name "/SPI5_MOSI_5V") (class "Default")
      (node (ref "EC3") (pin "5") (pinfunction "5_5") (pintype "passive"))
      (node (ref "EC4") (pin "5") (pinfunction "5_5") (pintype "passive"))
      (node (ref "EC5") (pin "5") (pinfunction "5_5") (pintype "passive"))
      (node (ref "U5") (pin "14") (pinfunction "DIN_14") (pintype "input"))
      (node (ref "U6") (pin "14") (pinfunction "DIN_14") (pintype "input"))
      (node (ref "U7") (pin "20") (pinfunction "B1_20") (pintype "bidirectional"))
    )
    (net (code "134") (name "/SPI5_SCK_3V3") (class "Default")
      (node (ref "EC10") (pin "3") (pinfunction "3_3") (pintype "passive"))
      (node (ref "EC11") (pin "3") (pinfunction "3_3") (pintype "passive"))
      (node (ref "EC12") (pin "3") (pinfunction "3_3") (pintype "passive"))
      (node (ref "EC13") (pin "3") (pinfunction "3_3") (pintype "passive"))
      (node (ref "EC6") (pin "3") (pinfunction "3_3") (pintype "passive"))
      (node (ref "EC7") (pin "3") (pinfunction "3_3") (pintype "passive"))
      (node (ref "EC8") (pin "3") (pinfunction "3_3") (pintype "passive"))
      (node (ref "EC9") (pin "3") (pinfunction "3_3") (pintype "passive"))
      (node (ref "U$1") (pin "1") (pinfunction "SCLK_1") (pintype "bidirectional"))
      (node (ref "U$4") (pin "P$70") (pinfunction "PF7_P$70") (pintype "bidirectional"))
      (node (ref "U$5") (pin "1") (pinfunction "SCLK_1") (pintype "bidirectional"))
      (node (ref "U7") (pin "4") (pinfunction "A3_4") (pintype "bidirectional"))
    )
    (net (code "135") (name "/SPI5_SCK_5V") (class "Default")
      (node (ref "EC3") (pin "3") (pinfunction "3_3") (pintype "passive"))
      (node (ref "EC4") (pin "3") (pinfunction "3_3") (pintype "passive"))
      (node (ref "EC5") (pin "3") (pinfunction "3_3") (pintype "passive"))
      (node (ref "U5") (pin "13") (pinfunction "SCLK_13") (pintype "input"))
      (node (ref "U6") (pin "13") (pinfunction "SCLK_13") (pintype "input"))
      (node (ref "U7") (pin "17") (pinfunction "B3_17") (pintype "bidirectional"))
    )
    (net (code "136") (name "/U1RX_3V3") (class "Default")
      (node (ref "JP2") (pin "5") (pinfunction "5_5") (pintype "passive"))
      (node (ref "U$4") (pin "P$24") (pinfunction "PB7_P$24") (pintype "bidirectional"))
    )
    (net (code "137") (name "/U1TX_3V3") (class "Default")
      (node (ref "JP2") (pin "4") (pinfunction "4_4") (pintype "passive"))
      (node (ref "U$4") (pin "P$52") (pinfunction "PA9_P$52") (pintype "bidirectional"))
    )
    (net (code "138") (name "GND") (class "Default")
      (node (ref "5V/2") (pin "1") (pinfunction "1_1") (pintype "passive"))
      (node (ref "5V/3") (pin "1") (pinfunction "1_1") (pintype "passive"))
      (node (ref "5V/4") (pin "1") (pinfunction "1_1") (pintype "passive"))
      (node (ref "A0") (pin "3") (pinfunction "3_3") (pintype "passive"))
      (node (ref "A1") (pin "3") (pinfunction "3_3") (pintype "passive"))
      (node (ref "A10") (pin "3") (pinfunction "3_3") (pintype "passive"))
      (node (ref "A11") (pin "3") (pinfunction "3_3") (pintype "passive"))
      (node (ref "A12") (pin "3") (pinfunction "3_3") (pintype "passive"))
      (node (ref "A13") (pin "3") (pinfunction "3_3") (pintype "passive"))
      (node (ref "A14") (pin "3") (pinfunction "3_3") (pintype "passive"))
      (node (ref "A2") (pin "3") (pinfunction "3_3") (pintype "passive"))
      (node (ref "A3") (pin "3") (pinfunction "3_3") (pintype "passive"))
      (node (ref "A4") (pin "3") (pinfunction "3_3") (pintype "passive"))
      (node (ref "A5") (pin "3") (pinfunction "3_3") (pintype "passive"))
      (node (ref "A6") (pin "3") (pinfunction "3_3") (pintype "passive"))
      (node (ref "A7") (pin "3") (pinfunction "3_3") (pintype "passive"))
      (node (ref "A8") (pin "3") (pinfunction "3_3") (pintype "passive"))
      (node (ref "A9") (pin "3") (pinfunction "3_3") (pintype "passive"))
      (node (ref "C1") (pin "2") (pinfunction "2_2") (pintype "passive"))
      (node (ref "C10") (pin "2") (pinfunction "2_2") (pintype "passive"))
      (node (ref "C11") (pin "2") (pinfunction "2_2") (pintype "passive"))
      (node (ref "C12") (pin "2") (pinfunction "2_2") (pintype "passive"))
      (node (ref "C13") (pin "2") (pinfunction "2_2") (pintype "passive"))
      (node (ref "C14") (pin "2") (pinfunction "2_2") (pintype "passive"))
      (node (ref "C15") (pin "2") (pinfunction "2_2") (pintype "passive"))
      (node (ref "C16") (pin "2") (pinfunction "2_2") (pintype "passive"))
      (node (ref "C17") (pin "2") (pinfunction "2_2") (pintype "passive"))
      (node (ref "C18") (pin "2") (pinfunction "2_2") (pintype "passive"))
      (node (ref "C19") (pin "2") (pinfunction "2_2") (pintype "passive"))
      (node (ref "C2") (pin "2") (pinfunction "2_2") (pintype "passive"))
      (node (ref "C20") (pin "2") (pinfunction "2_2") (pintype "passive"))
      (node (ref "C21") (pin "2") (pinfunction "2_2") (pintype "passive"))
      (node (ref "C22") (pin "2") (pinfunction "2_2") (pintype "passive"))
      (node (ref "C23") (pin "2") (pinfunction "2_2") (pintype "passive"))
      (node (ref "C24") (pin "2") (pinfunction "2_2") (pintype "passive"))
      (node (ref "C25") (pin "2") (pinfunction "2_2") (pintype "passive"))
      (node (ref "C26") (pin "2") (pinfunction "2_2") (pintype "passive"))
      (node (ref "C27") (pin "2") (pinfunction "2_2") (pintype "passive"))
      (node (ref "C28") (pin "2") (pinfunction "2_2") (pintype "passive"))
      (node (ref "C29") (pin "2") (pinfunction "2_2") (pintype "passive"))
      (node (ref "C3") (pin "-") (pinfunction "-_-") (pintype "passive"))
      (node (ref "C30") (pin "2") (pinfunction "2_2") (pintype "passive"))
      (node (ref "C31") (pin "2") (pinfunction "2_2") (pintype "passive"))
      (node (ref "C32") (pin "2") (pinfunction "2_2") (pintype "passive"))
      (node (ref "C33") (pin "2") (pinfunction "2_2") (pintype "passive"))
      (node (ref "C34") (pin "2") (pinfunction "2_2") (pintype "passive"))
      (node (ref "C35") (pin "2") (pinfunction "2_2") (pintype "passive"))
      (node (ref "C36") (pin "2") (pinfunction "2_2") (pintype "passive"))
      (node (ref "C37") (pin "2") (pinfunction "2_2") (pintype "passive"))
      (node (ref "C38") (pin "2") (pinfunction "2_2") (pintype "passive"))
      (node (ref "C39") (pin "2") (pinfunction "2_2") (pintype "passive"))
      (node (ref "C4") (pin "2") (pinfunction "2_2") (pintype "passive"))
      (node (ref "C40") (pin "2") (pinfunction "2_2") (pintype "passive"))
      (node (ref "C41") (pin "2") (pinfunction "2_2") (pintype "passive"))
      (node (ref "C42") (pin "2") (pinfunction "2_2") (pintype "passive"))
      (node (ref "C43") (pin "2") (pinfunction "2_2") (pintype "passive"))
      (node (ref "C44") (pin "2") (pinfunction "2_2") (pintype "passive"))
      (node (ref "C45") (pin "2") (pinfunction "2_2") (pintype "passive"))
      (node (ref "C46") (pin "2") (pinfunction "2_2") (pintype "passive"))
      (node (ref "C47") (pin "2") (pinfunction "2_2") (pintype "passive"))
      (node (ref "C48") (pin "2") (pinfunction "2_2") (pintype "passive"))
      (node (ref "C49") (pin "2") (pinfunction "2_2") (pintype "passive"))
      (node (ref "C5") (pin "2") (pinfunction "2_2") (pintype "passive"))
      (node (ref "C50") (pin "2") (pinfunction "2_2") (pintype "passive"))
      (node (ref "C6") (pin "2") (pinfunction "2_2") (pintype "passive"))
      (node (ref "C7") (pin "2") (pinfunction "2_2") (pintype "passive"))
      (node (ref "C8") (pin "2") (pinfunction "2_2") (pintype "passive"))
      (node (ref "C9") (pin "2") (pinfunction "2_2") (pintype "passive"))
      (node (ref "C95") (pin "2") (pinfunction "2_2") (pintype "passive"))
      (node (ref "C96") (pin "2") (pinfunction "2_2") (pintype "passive"))
      (node (ref "C97") (pin "2") (pinfunction "2_2") (pintype "passive"))
      (node (ref "C98") (pin "2") (pinfunction "2_2") (pintype "passive"))
      (node (ref "EC10") (pin "1") (pinfunction "1_1") (pintype "passive"))
      (node (ref "EC11") (pin "1") (pinfunction "1_1") (pintype "passive"))
      (node (ref "EC12") (pin "1") (pinfunction "1_1") (pintype "passive"))
      (node (ref "EC13") (pin "1") (pinfunction "1_1") (pintype "passive"))
      (node (ref "EC3") (pin "1") (pinfunction "1_1") (pintype "passive"))
      (node (ref "EC4") (pin "1") (pinfunction "1_1") (pintype "passive"))
      (node (ref "EC5") (pin "1") (pinfunction "1_1") (pintype "passive"))
      (node (ref "EC6") (pin "1") (pinfunction "1_1") (pintype "passive"))
      (node (ref "EC7") (pin "1") (pinfunction "1_1") (pintype "passive"))
      (node (ref "EC8") (pin "1") (pinfunction "1_1") (pintype "passive"))
      (node (ref "EC9") (pin "1") (pinfunction "1_1") (pintype "passive"))
      (node (ref "ENC0") (pin "1") (pinfunction "1_1") (pintype "passive"))
      (node (ref "ENC1") (pin "1") (pinfunction "1_1") (pintype "passive"))
      (node (ref "GYRO") (pin "1") (pinfunction "1_1") (pintype "passive"))
      (node (ref "H1") (pin "1") (pinfunction "1_1") (pintype "passive"))
      (node (ref "I2C") (pin "1") (pinfunction "1_1") (pintype "passive"))
      (node (ref "IC1") (pin "12") (pinfunction "GND_12") (pintype "power_in"))
      (node (ref "IC1") (pin "18") (pinfunction "G1_18") (pintype "input"))
      (node (ref "IC1") (pin "19") (pinfunction "G2_19") (pintype "input"))
      (node (ref "IO0") (pin "3") (pinfunction "3_3") (pintype "passive"))
      (node (ref "IO1") (pin "3") (pinfunction "3_3") (pintype "passive"))
      (node (ref "IO10") (pin "3") (pinfunction "3_3") (pintype "passive"))
      (node (ref "IO11") (pin "3") (pinfunction "3_3") (pintype "passive"))
      (node (ref "IO12") (pin "3") (pinfunction "3_3") (pintype "passive"))
      (node (ref "IO13") (pin "3") (pinfunction "3_3") (pintype "passive"))
      (node (ref "IO14") (pin "3") (pinfunction "3_3") (pintype "passive"))
      (node (ref "IO15") (pin "3") (pinfunction "3_3") (pintype "passive"))
      (node (ref "IO16") (pin "3") (pinfunction "3_3") (pintype "passive"))
      (node (ref "IO17") (pin "3") (pinfunction "3_3") (pintype "passive"))
      (node (ref "IO18") (pin "3") (pinfunction "3_3") (pintype "passive"))
      (node (ref "IO19") (pin "3") (pinfunction "3_3") (pintype "passive"))
      (node (ref "IO2") (pin "3") (pinfunction "3_3") (pintype "passive"))
      (node (ref "IO3") (pin "3") (pinfunction "3_3") (pintype "passive"))
      (node (ref "IO4") (pin "3") (pinfunction "3_3") (pintype "passive"))
      (node (ref "IO5") (pin "3") (pinfunction "3_3") (pintype "passive"))
      (node (ref "IO6") (pin "3") (pinfunction "3_3") (pintype "passive"))
      (node (ref "IO7") (pin "3") (pinfunction "3_3") (pintype "passive"))
      (node (ref "IO8") (pin "3") (pinfunction "3_3") (pintype "passive"))
      (node (ref "IO9") (pin "3") (pinfunction "3_3") (pintype "passive"))
      (node (ref "JP2") (pin "6") (pinfunction "6_6") (pintype "passive"))
      (node (ref "M0") (pin "1") (pinfunction "1_1") (pintype "passive"))
      (node (ref "M1") (pin "1") (pinfunction "1_1") (pintype "passive"))
      (node (ref "R11") (pin "2") (pinfunction "2_2") (pintype "passive"))
      (node (ref "R13") (pin "2") (pinfunction "2_2") (pintype "passive"))
      (node (ref "R15") (pin "2") (pinfunction "2_2") (pintype "passive"))
      (node (ref "R17") (pin "2") (pinfunction "2_2") (pintype "passive"))
      (node (ref "R19") (pin "2") (pinfunction "2_2") (pintype "passive"))
      (node (ref "R21") (pin "2") (pinfunction "2_2") (pintype "passive"))
      (node (ref "R23") (pin "2") (pinfunction "2_2") (pintype "passive"))
      (node (ref "R25") (pin "2") (pinfunction "2_2") (pintype "passive"))
      (node (ref "R27") (pin "2") (pinfunction "2_2") (pintype "passive"))
      (node (ref "R29") (pin "2") (pinfunction "2_2") (pintype "passive"))
      (node (ref "R31") (pin "2") (pinfunction "2_2") (pintype "passive"))
      (node (ref "R33") (pin "2") (pinfunction "2_2") (pintype "passive"))
      (node (ref "R35") (pin "2") (pinfunction "2_2") (pintype "passive"))
      (node (ref "R37") (pin "2") (pinfunction "2_2") (pintype "passive"))
      (node (ref "R7") (pin "2") (pinfunction "2_2") (pintype "passive"))
      (node (ref "R9") (pin "2") (pinfunction "2_2") (pintype "passive"))
      (node (ref "S0") (pin "3") (pinfunction "3_3") (pintype "passive"))
      (node (ref "S1") (pin "3") (pinfunction "3_3") (pintype "passive"))
      (node (ref "S10") (pin "3") (pinfunction "3_3") (pintype "passive"))
      (node (ref "S11") (pin "3") (pinfunction "3_3") (pintype "passive"))
      (node (ref "S12") (pin "3") (pinfunction "3_3") (pintype "passive"))
      (node (ref "S13") (pin "3") (pinfunction "3_3") (pintype "passive"))
      (node (ref "S14") (pin "3") (pinfunction "3_3") (pintype "passive"))
      (node (ref "S15") (pin "3") (pinfunction "3_3") (pintype "passive"))
      (node (ref "S16") (pin "3") (pinfunction "3_3") (pintype "passive"))
      (node (ref "S17") (pin "3") (pinfunction "3_3") (pintype "passive"))
      (node (ref "S18") (pin "3") (pinfunction "3_3") (pintype "passive"))
      (node (ref "S19") (pin "3") (pinfunction "3_3") (pintype "passive"))
      (node (ref "S2") (pin "3") (pinfunction "3_3") (pintype "passive"))
      (node (ref "S20") (pin "3") (pinfunction "3_3") (pintype "passive"))
      (node (ref "S21") (pin "3") (pinfunction "3_3") (pintype "passive"))
      (node (ref "S22") (pin "3") (pinfunction "3_3") (pintype "passive"))
      (node (ref "S23") (pin "3") (pinfunction "3_3") (pintype "passive"))
      (node (ref "S24") (pin "3") (pinfunction "3_3") (pintype "passive"))
      (node (ref "S25") (pin "3") (pinfunction "3_3") (pintype "passive"))
      (node (ref "S26") (pin "3") (pinfunction "3_3") (pintype "passive"))
      (node (ref "S27") (pin "3") (pinfunction "3_3") (pintype "passive"))
      (node (ref "S28") (pin "3") (pinfunction "3_3") (pintype "passive"))
      (node (ref "S29") (pin "3") (pinfunction "3_3") (pintype "passive"))
      (node (ref "S3") (pin "3") (pinfunction "3_3") (pintype "passive"))
      (node (ref "S30") (pin "3") (pinfunction "3_3") (pintype "passive"))
      (node (ref "S31") (pin "3") (pinfunction "3_3") (pintype "passive"))
      (node (ref "S4") (pin "3") (pinfunction "3_3") (pintype "passive"))
      (node (ref "S5") (pin "3") (pinfunction "3_3") (pintype "passive"))
      (node (ref "S6") (pin "3") (pinfunction "3_3") (pintype "passive"))
      (node (ref "S7") (pin "3") (pinfunction "3_3") (pintype "passive"))
      (node (ref "S8") (pin "3") (pinfunction "3_3") (pintype "passive"))
      (node (ref "S9") (pin "3") (pinfunction "3_3") (pintype "passive"))
      (node (ref "U$1") (pin "8") (pinfunction "GND_8") (pintype "bidirectional"))
      (node (ref "U$2") (pin "P$2") (pinfunction "GND_P$2") (pintype "bidirectional"))
      (node (ref "U$3") (pin "P$2") (pinfunction "GND_P$2") (pintype "bidirectional"))
      (node (ref "U$4") (pin "P$127") (pinfunction "GND_4_P$127") (pintype "bidirectional"))
      (node (ref "U$4") (pin "P$128") (pinfunction "GND_3_P$128") (pintype "bidirectional"))
      (node (ref "U$4") (pin "P$63") (pinfunction "GND_1_P$63") (pintype "bidirectional"))
      (node (ref "U$4") (pin "P$64") (pinfunction "GND_2_P$64") (pintype "bidirectional"))
      (node (ref "U$5") (pin "8") (pinfunction "GND_8") (pintype "bidirectional"))
      (node (ref "U1") (pin "1") (pinfunction "A0_1") (pintype "bidirectional"))
      (node (ref "U1") (pin "14") (pinfunction "GND_14") (pintype "power_in"))
      (node (ref "U1") (pin "2") (pinfunction "A1_2") (pintype "bidirectional"))
      (node (ref "U1") (pin "23") (pinfunction "#OE_23") (pintype "input"))
      (node (ref "U1") (pin "25") (pinfunction "EXTCLK_25") (pintype "input"))
      (node (ref "U1") (pin "3") (pinfunction "A2_3") (pintype "bidirectional"))
      (node (ref "U1") (pin "4") (pinfunction "A3_4") (pintype "bidirectional"))
      (node (ref "U2") (pin "14") (pinfunction "GND_14") (pintype "power_in"))
      (node (ref "U2") (pin "2") (pinfunction "A1_2") (pintype "bidirectional"))
      (node (ref "U2") (pin "23") (pinfunction "#OE_23") (pintype "input"))
      (node (ref "U2") (pin "25") (pinfunction "EXTCLK_25") (pintype "input"))
      (node (ref "U2") (pin "3") (pinfunction "A2_3") (pintype "bidirectional"))
      (node (ref "U2") (pin "4") (pinfunction "A3_4") (pintype "bidirectional"))
      (node (ref "U3") (pin "4") (pinfunction "GND_4") (pintype "bidirectional"))
      (node (ref "U4") (pin "11") (pinfunction "GND_11") (pintype "bidirectional"))
      (node (ref "U5") (pin "10") (pinfunction "GND_10") (pintype "passive"))
      (node (ref "U6") (pin "10") (pinfunction "GND_10") (pintype "passive"))
      (node (ref "U7") (pin "11") (pinfunction "GND_11") (pintype "bidirectional"))
      (node (ref "U8") (pin "11") (pinfunction "GND_11") (pintype "bidirectional"))
    )
    (net (code "139") (name "Net-(A0-Pad2)") (class "Default")
      (node (ref "A0") (pin "2") (pinfunction "2_2") (pintype "passive"))
      (node (ref "R6") (pin "2") (pinfunction "2_2") (pintype "passive"))
    )
    (net (code "140") (name "Net-(A1-Pad2)") (class "Default")
      (node (ref "A1") (pin "2") (pinfunction "2_2") (pintype "passive"))
      (node (ref "R8") (pin "2") (pinfunction "2_2") (pintype "passive"))
    )
    (net (code "141") (name "Net-(A2-Pad2)") (class "Default")
      (node (ref "A2") (pin "2") (pinfunction "2_2") (pintype "passive"))
      (node (ref "R10") (pin "2") (pinfunction "2_2") (pintype "passive"))
    )
    (net (code "142") (name "Net-(A3-Pad2)") (class "Default")
      (node (ref "A3") (pin "2") (pinfunction "2_2") (pintype "passive"))
      (node (ref "R30") (pin "2") (pinfunction "2_2") (pintype "passive"))
    )
    (net (code "143") (name "Net-(A4-Pad2)") (class "Default")
      (node (ref "A4") (pin "2") (pinfunction "2_2") (pintype "passive"))
      (node (ref "R12") (pin "2") (pinfunction "2_2") (pintype "passive"))
    )
    (net (code "144") (name "Net-(A5-Pad2)") (class "Default")
      (node (ref "A5") (pin "2") (pinfunction "2_2") (pintype "passive"))
      (node (ref "R14") (pin "2") (pinfunction "2_2") (pintype "passive"))
    )
    (net (code "145") (name "Net-(A6-Pad2)") (class "Default")
      (node (ref "A6") (pin "2") (pinfunction "2_2") (pintype "passive"))
      (node (ref "R16") (pin "2") (pinfunction "2_2") (pintype "passive"))
    )
    (net (code "146") (name "Net-(A7-Pad2)") (class "Default")
      (node (ref "A7") (pin "2") (pinfunction "2_2") (pintype "passive"))
      (node (ref "R32") (pin "2") (pinfunction "2_2") (pintype "passive"))
    )
    (net (code "147") (name "Net-(A8-Pad2)") (class "Default")
      (node (ref "A8") (pin "2") (pinfunction "2_2") (pintype "passive"))
      (node (ref "R18") (pin "2") (pinfunction "2_2") (pintype "passive"))
    )
    (net (code "148") (name "Net-(A9-Pad2)") (class "Default")
      (node (ref "A9") (pin "2") (pinfunction "2_2") (pintype "passive"))
      (node (ref "R20") (pin "2") (pinfunction "2_2") (pintype "passive"))
    )
    (net (code "149") (name "Net-(A10-Pad2)") (class "Default")
      (node (ref "A10") (pin "2") (pinfunction "2_2") (pintype "passive"))
      (node (ref "R22") (pin "2") (pinfunction "2_2") (pintype "passive"))
    )
    (net (code "150") (name "Net-(A11-Pad2)") (class "Default")
      (node (ref "A11") (pin "2") (pinfunction "2_2") (pintype "passive"))
      (node (ref "R34") (pin "2") (pinfunction "2_2") (pintype "passive"))
    )
    (net (code "151") (name "Net-(A12-Pad2)") (class "Default")
      (node (ref "A12") (pin "2") (pinfunction "2_2") (pintype "passive"))
      (node (ref "R24") (pin "2") (pinfunction "2_2") (pintype "passive"))
    )
    (net (code "152") (name "Net-(A13-Pad2)") (class "Default")
      (node (ref "A13") (pin "2") (pinfunction "2_2") (pintype "passive"))
      (node (ref "R26") (pin "2") (pinfunction "2_2") (pintype "passive"))
    )
    (net (code "153") (name "Net-(A14-Pad2)") (class "Default")
      (node (ref "A14") (pin "2") (pinfunction "2_2") (pintype "passive"))
      (node (ref "R28") (pin "2") (pinfunction "2_2") (pintype "passive"))
    )
    (net (code "154") (name "Net-(U$5-P0)") (class "Default")
      (node (ref "U$5") (pin "3") (pinfunction "P0_3") (pintype "bidirectional"))
      (node (ref "U8") (pin "1") (pinfunction "A1_1") (pintype "bidirectional"))
    )
    (net (code "155") (name "Net-(U$5-P1)") (class "Default")
      (node (ref "U$5") (pin "4") (pinfunction "P1_4") (pintype "bidirectional"))
      (node (ref "U8") (pin "3") (pinfunction "A2_3") (pintype "bidirectional"))
    )
    (net (code "156") (name "Net-(U$5-P2)") (class "Default")
      (node (ref "U$5") (pin "5") (pinfunction "P2_5") (pintype "bidirectional"))
      (node (ref "U8") (pin "4") (pinfunction "A3_4") (pintype "bidirectional"))
    )
    (net (code "157") (name "Net-(U$5-P3)") (class "Default")
      (node (ref "U$5") (pin "6") (pinfunction "P3_6") (pintype "bidirectional"))
      (node (ref "U8") (pin "5") (pinfunction "A4_5") (pintype "bidirectional"))
    )
    (net (code "158") (name "Net-(U$5-P4)") (class "Default")
      (node (ref "U$5") (pin "7") (pinfunction "P4_7") (pintype "bidirectional"))
      (node (ref "U8") (pin "6") (pinfunction "A5_6") (pintype "bidirectional"))
    )
    (net (code "159") (name "Net-(U$5-P5)") (class "Default")
      (node (ref "U$5") (pin "9") (pinfunction "P5_9") (pintype "bidirectional"))
      (node (ref "U8") (pin "7") (pinfunction "A6_7") (pintype "bidirectional"))
    )
    (net (code "160") (name "Net-(U$5-P6)") (class "Default")
      (node (ref "U$5") (pin "10") (pinfunction "P6_10") (pintype "bidirectional"))
      (node (ref "U8") (pin "8") (pinfunction "A7_8") (pintype "bidirectional"))
    )
    (net (code "161") (name "Net-(U$5-P7)") (class "Default")
      (node (ref "U$5") (pin "11") (pinfunction "P7_11") (pintype "bidirectional"))
      (node (ref "U8") (pin "9") (pinfunction "A8_9") (pintype "bidirectional"))
    )
    (net (code "162") (name "Net-(U3-EN)") (class "Default")
      (node (ref "C4") (pin "1") (pinfunction "1_1") (pintype "passive"))
      (node (ref "R1") (pin "1") (pinfunction "1_1") (pintype "passive"))
      (node (ref "U3") (pin "7") (pinfunction "VREF2_7") (pintype "bidirectional"))
      (node (ref "U3") (pin "8") (pinfunction "EN_8") (pintype "bidirectional"))
    )
    (net (code "163") (name "Net-(U5-REF)") (class "Default")
      (node (ref "C8") (pin "1") (pinfunction "1_1") (pintype "passive"))
      (node (ref "U5") (pin "9") (pinfunction "REF_9") (pintype "input"))
    )
    (net (code "164") (name "Net-(U6-REF)") (class "Default")
      (node (ref "C12") (pin "1") (pinfunction "1_1") (pintype "passive"))
      (node (ref "U6") (pin "9") (pinfunction "REF_9") (pintype "input"))
    )
    (net (code "165") (name "V+") (class "Default")
      (node (ref "C3") (pin "+") (pinfunction "+_+") (pintype "passive"))
      (node (ref "H7") (pin "1") (pinfunction "1_1") (pintype "passive"))
      (node (ref "R36") (pin "2") (pinfunction "2_2") (pintype "passive"))
      (node (ref "U$2") (pin "P$1") (pinfunction "VI_P$1") (pintype "bidirectional"))
      (node (ref "U$3") (pin "P$1") (pinfunction "VI_P$1") (pintype "bidirectional"))
    )
    (net (code "166") (name "unconnected-(EC3-Pad6)") (class "Default")
      (node (ref "EC3") (pin "6") (pinfunction "6_6") (pintype "passive"))
    )
    (net (code "167") (name "unconnected-(EC4-Pad6)") (class "Default")
      (node (ref "EC4") (pin "6") (pinfunction "6_6") (pintype "passive"))
    )
    (net (code "168") (name "unconnected-(EC5-Pad6)") (class "Default")
      (node (ref "EC5") (pin "6") (pinfunction "6_6") (pintype "passive"))
    )
    (net (code "169") (name "unconnected-(EC6-Pad6)") (class "Default")
      (node (ref "EC6") (pin "6") (pinfunction "6_6") (pintype "passive"))
    )
    (net (code "170") (name "unconnected-(EC7-Pad6)") (class "Default")
      (node (ref "EC7") (pin "6") (pinfunction "6_6") (pintype "passive"))
    )
    (net (code "171") (name "unconnected-(EC8-Pad6)") (class "Default")
      (node (ref "EC8") (pin "6") (pinfunction "6_6") (pintype "passive"))
    )
    (net (code "172") (name "unconnected-(EC9-Pad6)") (class "Default")
      (node (ref "EC9") (pin "6") (pinfunction "6_6") (pintype "passive"))
    )
    (net (code "173") (name "unconnected-(EC10-Pad6)") (class "Default")
      (node (ref "EC10") (pin "6") (pinfunction "6_6") (pintype "passive"))
    )
    (net (code "174") (name "unconnected-(IC1A-0-Pad1)") (class "Default")
      (node (ref "IC1") (pin "1") (pinfunction "0_1") (pintype "output"))
    )
    (net (code "175") (name "unconnected-(U$4A-BOOT0-PadP$21)") (class "Default")
      (node (ref "U$4") (pin "P$21") (pinfunction "BOOT0_P$21") (pintype "bidirectional"))
    )
    (net (code "176") (name "unconnected-(U$4A-PA11-PadP$50)") (class "Default")
      (node (ref "U$4") (pin "P$50") (pinfunction "PA11_P$50") (pintype "bidirectional"))
    )
    (net (code "177") (name "unconnected-(U$4A-PA12-PadP$49)") (class "Default")
      (node (ref "U$4") (pin "P$49") (pinfunction "PA12_P$49") (pintype "bidirectional"))
    )
    (net (code "178") (name "unconnected-(U$4A-PA13-PadP$48)") (class "Default")
      (node (ref "U$4") (pin "P$48") (pinfunction "PA13_P$48") (pintype "bidirectional"))
    )
    (net (code "179") (name "unconnected-(U$4A-PA14-PadP$47)") (class "Default")
      (node (ref "U$4") (pin "P$47") (pinfunction "PA14_P$47") (pintype "bidirectional"))
    )
    (net (code "180") (name "unconnected-(U$4A-PA15-PadP$46)") (class "Default")
      (node (ref "U$4") (pin "P$46") (pinfunction "PA15_P$46") (pintype "bidirectional"))
    )
    (net (code "181") (name "unconnected-(U$4A-PB3-PadP$28)") (class "Default")
      (node (ref "U$4") (pin "P$28") (pinfunction "PB3_P$28") (pintype "bidirectional"))
    )
    (net (code "182") (name "unconnected-(U$4A-PB5-PadP$26)") (class "Default")
      (node (ref "U$4") (pin "P$26") (pinfunction "PB5_P$26") (pintype "bidirectional"))
    )
    (net (code "183") (name "unconnected-(U$4A-PB6-PadP$23)") (class "Default")
      (node (ref "U$4") (pin "P$23") (pinfunction "PB6_P$23") (pintype "bidirectional"))
    )
    (net (code "184") (name "unconnected-(U$4A-PB8-PadP$19)") (class "Default")
      (node (ref "U$4") (pin "P$19") (pinfunction "PB8_P$19") (pintype "bidirectional"))
    )
    (net (code "185") (name "unconnected-(U$4A-PB9-PadP$20)") (class "Default")
      (node (ref "U$4") (pin "P$20") (pinfunction "PB9_P$20") (pintype "bidirectional"))
    )
    (net (code "186") (name "unconnected-(U$4A-PC6-PadP$57)") (class "Default")
      (node (ref "U$4") (pin "P$57") (pinfunction "PC6_P$57") (pintype "bidirectional"))
    )
    (net (code "187") (name "unconnected-(U$4A-PC7-PadP$56)") (class "Default")
      (node (ref "U$4") (pin "P$56") (pinfunction "PC7_P$56") (pintype "bidirectional"))
    )
    (net (code "188") (name "unconnected-(U$4A-PC10-PadP$45)") (class "Default")
      (node (ref "U$4") (pin "P$45") (pinfunction "PC10_P$45") (pintype "bidirectional"))
    )
    (net (code "189") (name "unconnected-(U$4A-PC14-PadP$9)") (class "Default")
      (node (ref "U$4") (pin "P$9") (pinfunction "PC14_P$9") (pintype "bidirectional"))
    )
    (net (code "190") (name "unconnected-(U$4A-PC15-PadP$10)") (class "Default")
      (node (ref "U$4") (pin "P$10") (pinfunction "PC15_P$10") (pintype "bidirectional"))
    )
    (net (code "191") (name "unconnected-(U$4A-PD0-PadP$42)") (class "Default")
      (node (ref "U$4") (pin "P$42") (pinfunction "PD0_P$42") (pintype "bidirectional"))
    )
    (net (code "192") (name "unconnected-(U$4A-PD1-PadP$41)") (class "Default")
      (node (ref "U$4") (pin "P$41") (pinfunction "PD1_P$41") (pintype "bidirectional"))
    )
    (net (code "193") (name "unconnected-(U$4A-PD3-PadP$39)") (class "Default")
      (node (ref "U$4") (pin "P$39") (pinfunction "PD3_P$39") (pintype "bidirectional"))
    )
    (net (code "194") (name "unconnected-(U$4A-PD6-PadP$36)") (class "Default")
      (node (ref "U$4") (pin "P$36") (pinfunction "PD6_P$36") (pintype "bidirectional"))
    )
    (net (code "195") (name "unconnected-(U$4A-PE0-PadP$17)") (class "Default")
      (node (ref "U$4") (pin "P$17") (pinfunction "PE0_P$17") (pintype "bidirectional"))
    )
    (net (code "196") (name "unconnected-(U$4A-PE1-PadP$18)") (class "Default")
      (node (ref "U$4") (pin "P$18") (pinfunction "PE1_P$18") (pintype "bidirectional"))
    )
    (net (code "197") (name "unconnected-(U$4A-PF0-PadP$7)") (class "Default")
      (node (ref "U$4") (pin "P$7") (pinfunction "PF0_P$7") (pintype "bidirectional"))
    )
    (net (code "198") (name "unconnected-(U$4A-PF1-PadP$8)") (class "Default")
      (node (ref "U$4") (pin "P$8") (pinfunction "PF1_P$8") (pintype "bidirectional"))
    )
    (net (code "199") (name "unconnected-(U$4A-PF2-PadP$5)") (class "Default")
      (node (ref "U$4") (pin "P$5") (pinfunction "PF2_P$5") (pintype "bidirectional"))
    )
    (net (code "200") (name "unconnected-(U$4A-PF3-PadP$6)") (class "Default")
      (node (ref "U$4") (pin "P$6") (pinfunction "PF3_P$6") (pintype "bidirectional"))
    )
    (net (code "201") (name "unconnected-(U$4A-PF4-PadP$3)") (class "Default")
      (node (ref "U$4") (pin "P$3") (pinfunction "PF4_P$3") (pintype "bidirectional"))
    )
    (net (code "202") (name "unconnected-(U$4A-PF5-PadP$4)") (class "Default")
      (node (ref "U$4") (pin "P$4") (pinfunction "PF5_P$4") (pintype "bidirectional"))
    )
    (net (code "203") (name "unconnected-(U$4A-PG4-PadP$62)") (class "Default")
      (node (ref "U$4") (pin "P$62") (pinfunction "PG4_P$62") (pintype "bidirectional"))
    )
    (net (code "204") (name "unconnected-(U$4A-PG5-PadP$61)") (class "Default")
      (node (ref "U$4") (pin "P$61") (pinfunction "PG5_P$61") (pintype "bidirectional"))
    )
    (net (code "205") (name "unconnected-(U$4A-PG6-PadP$60)") (class "Default")
      (node (ref "U$4") (pin "P$60") (pinfunction "PG6_P$60") (pintype "bidirectional"))
    )
    (net (code "206") (name "unconnected-(U$4A-PG7-PadP$59)") (class "Default")
      (node (ref "U$4") (pin "P$59") (pinfunction "PG7_P$59") (pintype "bidirectional"))
    )
    (net (code "207") (name "unconnected-(U$4A-PG8-PadP$58)") (class "Default")
      (node (ref "U$4") (pin "P$58") (pinfunction "PG8_P$58") (pintype "bidirectional"))
    )
    (net (code "208") (name "unconnected-(U$4A-PG10-PadP$34)") (class "Default")
      (node (ref "U$4") (pin "P$34") (pinfunction "PG10_P$34") (pintype "bidirectional"))
    )
    (net (code "209") (name "unconnected-(U$4A-PG11-PadP$31)") (class "Default")
      (node (ref "U$4") (pin "P$31") (pinfunction "PG11_P$31") (pintype "bidirectional"))
    )
    (net (code "210") (name "unconnected-(U$4A-PG12-PadP$32)") (class "Default")
      (node (ref "U$4") (pin "P$32") (pinfunction "PG12_P$32") (pintype "bidirectional"))
    )
    (net (code "211") (name "unconnected-(U$4A-PG13-PadP$29)") (class "Default")
      (node (ref "U$4") (pin "P$29") (pinfunction "PG13_P$29") (pintype "bidirectional"))
    )
    (net (code "212") (name "unconnected-(U$4A-PG14-PadP$30)") (class "Default")
      (node (ref "U$4") (pin "P$30") (pinfunction "PG14_P$30") (pintype "bidirectional"))
    )
    (net (code "213") (name "unconnected-(U$4A-PG15-PadP$27)") (class "Default")
      (node (ref "U$4") (pin "P$27") (pinfunction "PG15_P$27") (pintype "bidirectional"))
    )
    (net (code "214") (name "unconnected-(U$4A-VDD-PadP$22)") (class "Default")
      (node (ref "U$4") (pin "P$22") (pinfunction "VDD_P$22") (pintype "bidirectional"))
    )
    (net (code "215") (name "unconnected-(U$4B-3V3_1-PadP$65)") (class "Default")
      (node (ref "U$4") (pin "P$65") (pinfunction "3V3_1_P$65") (pintype "bidirectional"))
    )
    (net (code "216") (name "unconnected-(U$4B-3V3_2-PadP$66)") (class "Default")
      (node (ref "U$4") (pin "P$66") (pinfunction "3V3_2_P$66") (pintype "bidirectional"))
    )
    (net (code "217") (name "unconnected-(U$4B-GND_1-PadP$75)") (class "Default")
      (node (ref "U$4") (pin "P$75") (pinfunction "GND_1_P$75") (pintype "bidirectional"))
    )
    (net (code "218") (name "unconnected-(U$4B-GND_2-PadP$93)") (class "Default")
      (node (ref "U$4") (pin "P$93") (pinfunction "GND_2_P$93") (pintype "bidirectional"))
    )
    (net (code "219") (name "unconnected-(U$4B-NRST-PadP$76)") (class "Default")
      (node (ref "U$4") (pin "P$76") (pinfunction "NRST_P$76") (pintype "bidirectional"))
    )
    (net (code "220") (name "unconnected-(U$4B-PA0-PadP$82)") (class "Default")
      (node (ref "U$4") (pin "P$82") (pinfunction "PA0_P$82") (pintype "bidirectional"))
    )
    (net (code "221") (name "unconnected-(U$4B-PA1-PadP$81)") (class "Default")
      (node (ref "U$4") (pin "P$81") (pinfunction "PA1_P$81") (pintype "bidirectional"))
    )
    (net (code "222") (name "unconnected-(U$4B-PA2-PadP$84)") (class "Default")
      (node (ref "U$4") (pin "P$84") (pinfunction "PA2_P$84") (pintype "bidirectional"))
    )
    (net (code "223") (name "unconnected-(U$4B-PA3-PadP$83)") (class "Default")
      (node (ref "U$4") (pin "P$83") (pinfunction "PA3_P$83") (pintype "bidirectional"))
    )
    (net (code "224") (name "unconnected-(U$4B-PA4-PadP$86)") (class "Default")
      (node (ref "U$4") (pin "P$86") (pinfunction "PA4_P$86") (pintype "bidirectional"))
    )
    (net (code "225") (name "unconnected-(U$4B-PA6-PadP$88)") (class "Default")
      (node (ref "U$4") (pin "P$88") (pinfunction "PA6_P$88") (pintype "bidirectional"))
    )
    (net (code "226") (name "unconnected-(U$4B-PA7-PadP$87)") (class "Default")
      (node (ref "U$4") (pin "P$87") (pinfunction "PA7_P$87") (pintype "bidirectional"))
    )
    (net (code "227") (name "unconnected-(U$4B-PB0-PadP$92)") (class "Default")
      (node (ref "U$4") (pin "P$92") (pinfunction "PB0_P$92") (pintype "bidirectional"))
    )
    (net (code "228") (name "unconnected-(U$4B-PB1-PadP$91)") (class "Default")
      (node (ref "U$4") (pin "P$91") (pinfunction "PB1_P$91") (pintype "bidirectional"))
    )
    (net (code "229") (name "unconnected-(U$4B-PB2-PadP$94)") (class "Default")
      (node (ref "U$4") (pin "P$94") (pinfunction "PB2_P$94") (pintype "bidirectional"))
    )
    (net (code "230") (name "unconnected-(U$4B-PB10-PadP$112)") (class "Default")
      (node (ref "U$4") (pin "P$112") (pinfunction "PB10_P$112") (pintype "bidirectional"))
    )
    (net (code "231") (name "unconnected-(U$4B-PB11-PadP$111)") (class "Default")
      (node (ref "U$4") (pin "P$111") (pinfunction "PB11_P$111") (pintype "bidirectional"))
    )
    (net (code "232") (name "unconnected-(U$4B-PB12-PadP$114)") (class "Default")
      (node (ref "U$4") (pin "P$114") (pinfunction "PB12_P$114") (pintype "bidirectional"))
    )
    (net (code "233") (name "unconnected-(U$4B-PB13-PadP$113)") (class "Default")
      (node (ref "U$4") (pin "P$113") (pinfunction "PB13_P$113") (pintype "bidirectional"))
    )
    (net (code "234") (name "unconnected-(U$4B-PB14-PadP$116)") (class "Default")
      (node (ref "U$4") (pin "P$116") (pinfunction "PB14_P$116") (pintype "bidirectional"))
    )
    (net (code "235") (name "unconnected-(U$4B-PB15-PadP$115)") (class "Default")
      (node (ref "U$4") (pin "P$115") (pinfunction "PB15_P$115") (pintype "bidirectional"))
    )
    (net (code "236") (name "unconnected-(U$4B-PC0-PadP$78)") (class "Default")
      (node (ref "U$4") (pin "P$78") (pinfunction "PC0_P$78") (pintype "bidirectional"))
    )
    (net (code "237") (name "unconnected-(U$4B-PC1-PadP$77)") (class "Default")
      (node (ref "U$4") (pin "P$77") (pinfunction "PC1_P$77") (pintype "bidirectional"))
    )
    (net (code "238") (name "unconnected-(U$4B-PC2-PadP$80)") (class "Default")
      (node (ref "U$4") (pin "P$80") (pinfunction "PC2_P$80") (pintype "bidirectional"))
    )
    (net (code "239") (name "unconnected-(U$4B-PC4-PadP$90)") (class "Default")
      (node (ref "U$4") (pin "P$90") (pinfunction "PC4_P$90") (pintype "bidirectional"))
    )
    (net (code "240") (name "unconnected-(U$4B-PC5-PadP$89)") (class "Default")
      (node (ref "U$4") (pin "P$89") (pinfunction "PC5_P$89") (pintype "bidirectional"))
    )
    (net (code "241") (name "unconnected-(U$4B-PD8-PadP$118)") (class "Default")
      (node (ref "U$4") (pin "P$118") (pinfunction "PD8_P$118") (pintype "bidirectional"))
    )
    (net (code "242") (name "unconnected-(U$4B-PD9-PadP$117)") (class "Default")
      (node (ref "U$4") (pin "P$117") (pinfunction "PD9_P$117") (pintype "bidirectional"))
    )
    (net (code "243") (name "unconnected-(U$4B-PD10-PadP$120)") (class "Default")
      (node (ref "U$4") (pin "P$120") (pinfunction "PD10_P$120") (pintype "bidirectional"))
    )
    (net (code "244") (name "unconnected-(U$4B-PD11-PadP$119)") (class "Default")
      (node (ref "U$4") (pin "P$119") (pinfunction "PD11_P$119") (pintype "bidirectional"))
    )
    (net (code "245") (name "unconnected-(U$4B-PD12-PadP$122)") (class "Default")
      (node (ref "U$4") (pin "P$122") (pinfunction "PD12_P$122") (pintype "bidirectional"))
    )
    (net (code "246") (name "unconnected-(U$4B-PD13-PadP$121)") (class "Default")
      (node (ref "U$4") (pin "P$121") (pinfunction "PD13_P$121") (pintype "bidirectional"))
    )
    (net (code "247") (name "unconnected-(U$4B-PD14-PadP$124)") (class "Default")
      (node (ref "U$4") (pin "P$124") (pinfunction "PD14_P$124") (pintype "bidirectional"))
    )
    (net (code "248") (name "unconnected-(U$4B-PD15-PadP$123)") (class "Default")
      (node (ref "U$4") (pin "P$123") (pinfunction "PD15_P$123") (pintype "bidirectional"))
    )
    (net (code "249") (name "unconnected-(U$4B-PE7-PadP$101)") (class "Default")
      (node (ref "U$4") (pin "P$101") (pinfunction "PE7_P$101") (pintype "bidirectional"))
    )
    (net (code "250") (name "unconnected-(U$4B-PE8-PadP$104)") (class "Default")
      (node (ref "U$4") (pin "P$104") (pinfunction "PE8_P$104") (pintype "bidirectional"))
    )
    (net (code "251") (name "unconnected-(U$4B-PE9-PadP$103)") (class "Default")
      (node (ref "U$4") (pin "P$103") (pinfunction "PE9_P$103") (pintype "bidirectional"))
    )
    (net (code "252") (name "unconnected-(U$4B-PE10-PadP$106)") (class "Default")
      (node (ref "U$4") (pin "P$106") (pinfunction "PE10_P$106") (pintype "bidirectional"))
    )
    (net (code "253") (name "unconnected-(U$4B-PE11-PadP$105)") (class "Default")
      (node (ref "U$4") (pin "P$105") (pinfunction "PE11_P$105") (pintype "bidirectional"))
    )
    (net (code "254") (name "unconnected-(U$4B-PE12-PadP$108)") (class "Default")
      (node (ref "U$4") (pin "P$108") (pinfunction "PE12_P$108") (pintype "bidirectional"))
    )
    (net (code "255") (name "unconnected-(U$4B-PE13-PadP$107)") (class "Default")
      (node (ref "U$4") (pin "P$107") (pinfunction "PE13_P$107") (pintype "bidirectional"))
    )
    (net (code "256") (name "unconnected-(U$4B-PE14-PadP$110)") (class "Default")
      (node (ref "U$4") (pin "P$110") (pinfunction "PE14_P$110") (pintype "bidirectional"))
    )
    (net (code "257") (name "unconnected-(U$4B-PE15-PadP$109)") (class "Default")
      (node (ref "U$4") (pin "P$109") (pinfunction "PE15_P$109") (pintype "bidirectional"))
    )
    (net (code "258") (name "unconnected-(U$4B-PF10-PadP$71)") (class "Default")
      (node (ref "U$4") (pin "P$71") (pinfunction "PF10_P$71") (pintype "bidirectional"))
    )
    (net (code "259") (name "unconnected-(U$4B-PF11-PadP$96)") (class "Default")
      (node (ref "U$4") (pin "P$96") (pinfunction "PF11_P$96") (pintype "bidirectional"))
    )
    (net (code "260") (name "unconnected-(U$4B-PF12-PadP$95)") (class "Default")
      (node (ref "U$4") (pin "P$95") (pinfunction "PF12_P$95") (pintype "bidirectional"))
    )
    (net (code "261") (name "unconnected-(U$4B-PF13-PadP$98)") (class "Default")
      (node (ref "U$4") (pin "P$98") (pinfunction "PF13_P$98") (pintype "bidirectional"))
    )
    (net (code "262") (name "unconnected-(U$4B-PF14-PadP$97)") (class "Default")
      (node (ref "U$4") (pin "P$97") (pinfunction "PF14_P$97") (pintype "bidirectional"))
    )
    (net (code "263") (name "unconnected-(U$4B-PF15-PadP$100)") (class "Default")
      (node (ref "U$4") (pin "P$100") (pinfunction "PF15_P$100") (pintype "bidirectional"))
    )
    (net (code "264") (name "unconnected-(U$4B-PG0-PadP$99)") (class "Default")
      (node (ref "U$4") (pin "P$99") (pinfunction "PG0_P$99") (pintype "bidirectional"))
    )
    (net (code "265") (name "unconnected-(U$4B-PG1-PadP$102)") (class "Default")
      (node (ref "U$4") (pin "P$102") (pinfunction "PG1_P$102") (pintype "bidirectional"))
    )
    (net (code "266") (name "unconnected-(U$4B-PH0-PadP$74)") (class "Default")
      (node (ref "U$4") (pin "P$74") (pinfunction "PH0_P$74") (pintype "bidirectional"))
    )
    (net (code "267") (name "unconnected-(U$4B-PH1-PadP$73)") (class "Default")
      (node (ref "U$4") (pin "P$73") (pinfunction "PH1_P$73") (pintype "bidirectional"))
    )
    (net (code "268") (name "unconnected-(U5-~{EOC}-Pad16)") (class "Default")
      (node (ref "U5") (pin "16") (pinfunction "~{EOC}_16") (pintype "output"))
    )
    (net (code "269") (name "unconnected-(U6-~{EOC}-Pad16)") (class "Default")
      (node (ref "U6") (pin "16") (pinfunction "~{EOC}_16") (pintype "output"))
    )
  )
)
